# SDRAM_DDR3_4x16.net
KiCad netlist of a schematic drawn in Altium Designer
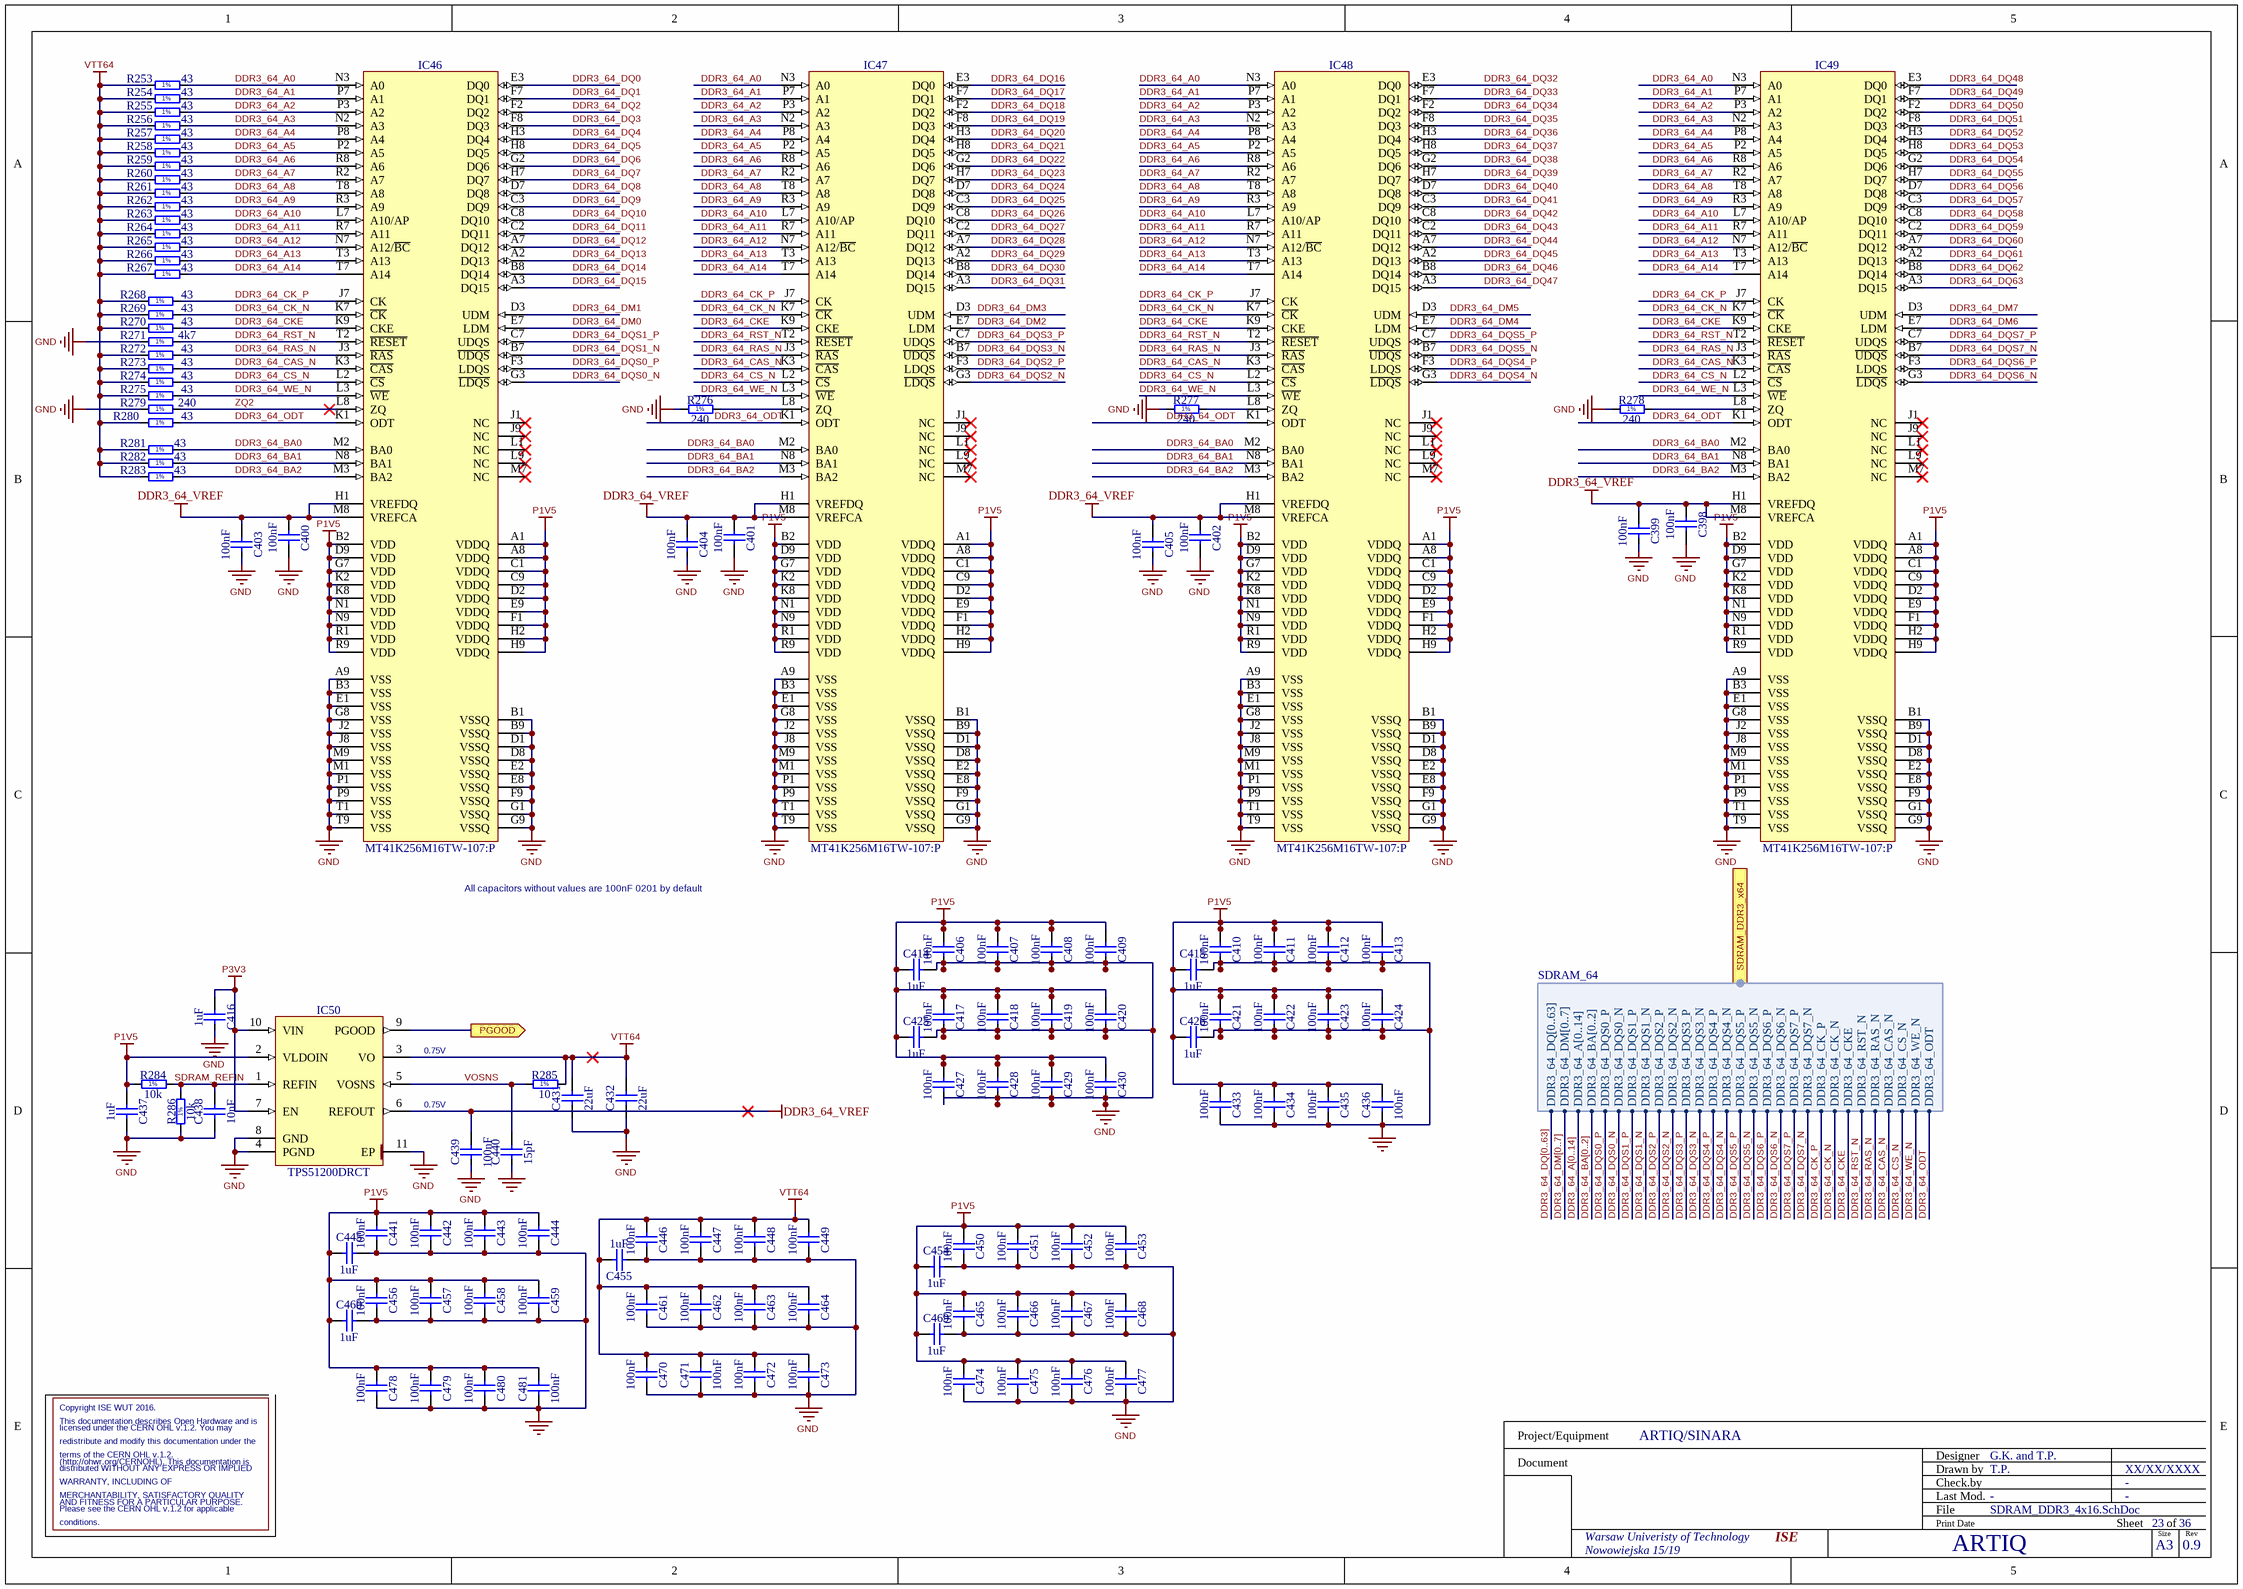
[diagram p0: SDRAM_DDR3_4x16.SchDoc]

(export (version "E")
  (design (tool "Eeschema 10.0.6"))
  (components
    (comp (ref "C398")
      (value "100nF")
      (footprint "CAPC0603X33N")
      (description "Non-polarised capacitor")
      (fields
        (field (name "MANUFACTURER PART NUMBER") "CC0201_100NF_6.3V_10%_X5R")
        (field (name "MANUFACTURER") "GENERIC")
        (field (name "AUTHOR") "CERN DEM JLC")
      )
      (libsource (lib "Capacitors") (part "Capacitor - non polarized"))
    )
    (comp (ref "C399")
      (value "100nF")
      (footprint "CAPC0603X33N")
      (description "Non-polarised capacitor")
      (fields
        (field (name "MANUFACTURER PART NUMBER") "CC0201_100NF_6.3V_10%_X5R")
        (field (name "MANUFACTURER") "GENERIC")
        (field (name "AUTHOR") "CERN DEM JLC")
      )
      (libsource (lib "Capacitors") (part "Capacitor - non polarized"))
    )
    (comp (ref "C400")
      (value "100nF")
      (footprint "CAPC0603X33N")
      (description "Non-polarised capacitor")
      (fields
        (field (name "MANUFACTURER PART NUMBER") "CC0201_100NF_6.3V_10%_X5R")
        (field (name "MANUFACTURER") "GENERIC")
        (field (name "AUTHOR") "CERN DEM JLC")
      )
      (libsource (lib "Capacitors") (part "Capacitor - non polarized"))
    )
    (comp (ref "C401")
      (value "100nF")
      (footprint "CAPC0603X33N")
      (description "Non-polarised capacitor")
      (fields
        (field (name "MANUFACTURER PART NUMBER") "CC0201_100NF_6.3V_10%_X5R")
        (field (name "MANUFACTURER") "GENERIC")
        (field (name "AUTHOR") "CERN DEM JLC")
      )
      (libsource (lib "Capacitors") (part "Capacitor - non polarized"))
    )
    (comp (ref "C402")
      (value "100nF")
      (footprint "CAPC0603X33N")
      (description "Non-polarised capacitor")
      (fields
        (field (name "MANUFACTURER PART NUMBER") "CC0201_100NF_6.3V_10%_X5R")
        (field (name "MANUFACTURER") "GENERIC")
        (field (name "AUTHOR") "CERN DEM JLC")
      )
      (libsource (lib "Capacitors") (part "Capacitor - non polarized"))
    )
    (comp (ref "C403")
      (value "100nF")
      (footprint "CAPC0603X33N")
      (description "Non-polarised capacitor")
      (fields
        (field (name "MANUFACTURER PART NUMBER") "CC0201_100NF_6.3V_10%_X5R")
        (field (name "MANUFACTURER") "GENERIC")
        (field (name "AUTHOR") "CERN DEM JLC")
      )
      (libsource (lib "Capacitors") (part "Capacitor - non polarized"))
    )
    (comp (ref "C404")
      (value "100nF")
      (footprint "CAPC0603X33N")
      (description "Non-polarised capacitor")
      (fields
        (field (name "MANUFACTURER PART NUMBER") "CC0201_100NF_6.3V_10%_X5R")
        (field (name "MANUFACTURER") "GENERIC")
        (field (name "AUTHOR") "CERN DEM JLC")
      )
      (libsource (lib "Capacitors") (part "Capacitor - non polarized"))
    )
    (comp (ref "C405")
      (value "100nF")
      (footprint "CAPC0603X33N")
      (description "Non-polarised capacitor")
      (fields
        (field (name "MANUFACTURER PART NUMBER") "CC0201_100NF_6.3V_10%_X5R")
        (field (name "MANUFACTURER") "GENERIC")
        (field (name "AUTHOR") "CERN DEM JLC")
      )
      (libsource (lib "Capacitors") (part "Capacitor - non polarized"))
    )
    (comp (ref "C406")
      (value "100nF")
      (footprint "CAPC0603X33N")
      (description "Non-polarised capacitor")
      (fields
        (field (name "MANUFACTURER PART NUMBER") "CC0201_100NF_6.3V_10%_X5R")
        (field (name "MANUFACTURER") "GENERIC")
        (field (name "AUTHOR") "CERN DEM JLC")
      )
      (libsource (lib "Capacitors") (part "Capacitor - non polarized"))
    )
    (comp (ref "C407")
      (value "100nF")
      (footprint "CAPC0603X33N")
      (description "Non-polarised capacitor")
      (fields
        (field (name "MANUFACTURER PART NUMBER") "CC0201_100NF_6.3V_10%_X5R")
        (field (name "MANUFACTURER") "GENERIC")
        (field (name "AUTHOR") "CERN DEM JLC")
      )
      (libsource (lib "Capacitors") (part "Capacitor - non polarized"))
    )
    (comp (ref "C408")
      (value "100nF")
      (footprint "CAPC0603X33N")
      (description "Non-polarised capacitor")
      (fields
        (field (name "MANUFACTURER PART NUMBER") "CC0201_100NF_6.3V_10%_X5R")
        (field (name "MANUFACTURER") "GENERIC")
        (field (name "AUTHOR") "CERN DEM JLC")
      )
      (libsource (lib "Capacitors") (part "Capacitor - non polarized"))
    )
    (comp (ref "C409")
      (value "100nF")
      (footprint "CAPC0603X33N")
      (description "Non-polarised capacitor")
      (fields
        (field (name "MANUFACTURER PART NUMBER") "CC0201_100NF_6.3V_10%_X5R")
        (field (name "MANUFACTURER") "GENERIC")
        (field (name "AUTHOR") "CERN DEM JLC")
      )
      (libsource (lib "Capacitors") (part "Capacitor - non polarized"))
    )
    (comp (ref "C410")
      (value "100nF")
      (footprint "CAPC0603X33N")
      (description "Non-polarised capacitor")
      (fields
        (field (name "MANUFACTURER PART NUMBER") "CC0201_100NF_6.3V_10%_X5R")
        (field (name "MANUFACTURER") "GENERIC")
        (field (name "AUTHOR") "CERN DEM JLC")
      )
      (libsource (lib "Capacitors") (part "Capacitor - non polarized"))
    )
    (comp (ref "C411")
      (value "100nF")
      (footprint "CAPC0603X33N")
      (description "Non-polarised capacitor")
      (fields
        (field (name "MANUFACTURER PART NUMBER") "CC0201_100NF_6.3V_10%_X5R")
        (field (name "MANUFACTURER") "GENERIC")
        (field (name "AUTHOR") "CERN DEM JLC")
      )
      (libsource (lib "Capacitors") (part "Capacitor - non polarized"))
    )
    (comp (ref "C412")
      (value "100nF")
      (footprint "CAPC0603X33N")
      (description "Non-polarised capacitor")
      (fields
        (field (name "MANUFACTURER PART NUMBER") "CC0201_100NF_6.3V_10%_X5R")
        (field (name "MANUFACTURER") "GENERIC")
        (field (name "AUTHOR") "CERN DEM JLC")
      )
      (libsource (lib "Capacitors") (part "Capacitor - non polarized"))
    )
    (comp (ref "C413")
      (value "100nF")
      (footprint "CAPC0603X33N")
      (description "Non-polarised capacitor")
      (fields
        (field (name "MANUFACTURER PART NUMBER") "CC0201_100NF_6.3V_10%_X5R")
        (field (name "MANUFACTURER") "GENERIC")
        (field (name "AUTHOR") "CERN DEM JLC")
      )
      (libsource (lib "Capacitors") (part "Capacitor - non polarized"))
    )
    (comp (ref "C414")
      (value "1uF")
      (footprint "CAPC1005X55N")
      (description "Non-polarised capacitor")
      (fields
        (field (name "MANUFACTURER PART NUMBER") "CC0402_1UF_16V_10%_X5R")
        (field (name "MANUFACTURER") "GENERIC")
        (field (name "AUTHOR") "CERN DEM JLC")
      )
      (libsource (lib "Capacitors") (part "Capacitor - non polarized"))
    )
    (comp (ref "C415")
      (value "1uF")
      (footprint "CAPC1005X55N")
      (description "Non-polarised capacitor")
      (fields
        (field (name "MANUFACTURER PART NUMBER") "CC0402_1UF_16V_10%_X5R")
        (field (name "MANUFACTURER") "GENERIC")
        (field (name "AUTHOR") "CERN DEM JLC")
      )
      (libsource (lib "Capacitors") (part "Capacitor - non polarized"))
    )
    (comp (ref "C416")
      (value "1uF")
      (footprint "CAPC1005X55N")
      (description "Non-polarised capacitor")
      (fields
        (field (name "MANUFACTURER PART NUMBER") "CC0402_1UF_16V_10%_X5R")
        (field (name "MANUFACTURER") "GENERIC")
        (field (name "AUTHOR") "CERN DEM JLC")
      )
      (libsource (lib "Capacitors") (part "Capacitor - non polarized"))
    )
    (comp (ref "C417")
      (value "100nF")
      (footprint "CAPC0603X33N")
      (description "Non-polarised capacitor")
      (fields
        (field (name "MANUFACTURER PART NUMBER") "CC0201_100NF_6.3V_10%_X5R")
        (field (name "MANUFACTURER") "GENERIC")
        (field (name "AUTHOR") "CERN DEM JLC")
      )
      (libsource (lib "Capacitors") (part "Capacitor - non polarized"))
    )
    (comp (ref "C418")
      (value "100nF")
      (footprint "CAPC0603X33N")
      (description "Non-polarised capacitor")
      (fields
        (field (name "MANUFACTURER PART NUMBER") "CC0201_100NF_6.3V_10%_X5R")
        (field (name "MANUFACTURER") "GENERIC")
        (field (name "AUTHOR") "CERN DEM JLC")
      )
      (libsource (lib "Capacitors") (part "Capacitor - non polarized"))
    )
    (comp (ref "C419")
      (value "100nF")
      (footprint "CAPC0603X33N")
      (description "Non-polarised capacitor")
      (fields
        (field (name "MANUFACTURER PART NUMBER") "CC0201_100NF_6.3V_10%_X5R")
        (field (name "MANUFACTURER") "GENERIC")
        (field (name "AUTHOR") "CERN DEM JLC")
      )
      (libsource (lib "Capacitors") (part "Capacitor - non polarized"))
    )
    (comp (ref "C420")
      (value "100nF")
      (footprint "CAPC0603X33N")
      (description "Non-polarised capacitor")
      (fields
        (field (name "MANUFACTURER PART NUMBER") "CC0201_100NF_6.3V_10%_X5R")
        (field (name "MANUFACTURER") "GENERIC")
        (field (name "AUTHOR") "CERN DEM JLC")
      )
      (libsource (lib "Capacitors") (part "Capacitor - non polarized"))
    )
    (comp (ref "C421")
      (value "100nF")
      (footprint "CAPC0603X33N")
      (description "Non-polarised capacitor")
      (fields
        (field (name "MANUFACTURER PART NUMBER") "CC0201_100NF_6.3V_10%_X5R")
        (field (name "MANUFACTURER") "GENERIC")
        (field (name "AUTHOR") "CERN DEM JLC")
      )
      (libsource (lib "Capacitors") (part "Capacitor - non polarized"))
    )
    (comp (ref "C422")
      (value "100nF")
      (footprint "CAPC0603X33N")
      (description "Non-polarised capacitor")
      (fields
        (field (name "MANUFACTURER PART NUMBER") "CC0201_100NF_6.3V_10%_X5R")
        (field (name "MANUFACTURER") "GENERIC")
        (field (name "AUTHOR") "CERN DEM JLC")
      )
      (libsource (lib "Capacitors") (part "Capacitor - non polarized"))
    )
    (comp (ref "C423")
      (value "100nF")
      (footprint "CAPC0603X33N")
      (description "Non-polarised capacitor")
      (fields
        (field (name "MANUFACTURER PART NUMBER") "CC0201_100NF_6.3V_10%_X5R")
        (field (name "MANUFACTURER") "GENERIC")
        (field (name "AUTHOR") "CERN DEM JLC")
      )
      (libsource (lib "Capacitors") (part "Capacitor - non polarized"))
    )
    (comp (ref "C424")
      (value "100nF")
      (footprint "CAPC0603X33N")
      (description "Non-polarised capacitor")
      (fields
        (field (name "MANUFACTURER PART NUMBER") "CC0201_100NF_6.3V_10%_X5R")
        (field (name "MANUFACTURER") "GENERIC")
        (field (name "AUTHOR") "CERN DEM JLC")
      )
      (libsource (lib "Capacitors") (part "Capacitor - non polarized"))
    )
    (comp (ref "C425")
      (value "1uF")
      (footprint "CAPC1005X55N")
      (description "Non-polarised capacitor")
      (fields
        (field (name "MANUFACTURER PART NUMBER") "CC0402_1UF_16V_10%_X5R")
        (field (name "MANUFACTURER") "GENERIC")
        (field (name "AUTHOR") "CERN DEM JLC")
      )
      (libsource (lib "Capacitors") (part "Capacitor - non polarized"))
    )
    (comp (ref "C426")
      (value "1uF")
      (footprint "CAPC1005X55N")
      (description "Non-polarised capacitor")
      (fields
        (field (name "MANUFACTURER PART NUMBER") "CC0402_1UF_16V_10%_X5R")
        (field (name "MANUFACTURER") "GENERIC")
        (field (name "AUTHOR") "CERN DEM JLC")
      )
      (libsource (lib "Capacitors") (part "Capacitor - non polarized"))
    )
    (comp (ref "C427")
      (value "100nF")
      (footprint "CAPC0603X33N")
      (description "Non-polarised capacitor")
      (fields
        (field (name "MANUFACTURER PART NUMBER") "CC0201_100NF_6.3V_10%_X5R")
        (field (name "MANUFACTURER") "GENERIC")
        (field (name "AUTHOR") "CERN DEM JLC")
      )
      (libsource (lib "Capacitors") (part "Capacitor - non polarized"))
    )
    (comp (ref "C428")
      (value "100nF")
      (footprint "CAPC0603X33N")
      (description "Non-polarised capacitor")
      (fields
        (field (name "MANUFACTURER PART NUMBER") "CC0201_100NF_6.3V_10%_X5R")
        (field (name "MANUFACTURER") "GENERIC")
        (field (name "AUTHOR") "CERN DEM JLC")
      )
      (libsource (lib "Capacitors") (part "Capacitor - non polarized"))
    )
    (comp (ref "C429")
      (value "100nF")
      (footprint "CAPC0603X33N")
      (description "Non-polarised capacitor")
      (fields
        (field (name "MANUFACTURER PART NUMBER") "CC0201_100NF_6.3V_10%_X5R")
        (field (name "MANUFACTURER") "GENERIC")
        (field (name "AUTHOR") "CERN DEM JLC")
      )
      (libsource (lib "Capacitors") (part "Capacitor - non polarized"))
    )
    (comp (ref "C430")
      (value "100nF")
      (footprint "CAPC0603X33N")
      (description "Non-polarised capacitor")
      (fields
        (field (name "MANUFACTURER PART NUMBER") "CC0201_100NF_6.3V_10%_X5R")
        (field (name "MANUFACTURER") "GENERIC")
        (field (name "AUTHOR") "CERN DEM JLC")
      )
      (libsource (lib "Capacitors") (part "Capacitor - non polarized"))
    )
    (comp (ref "C431")
      (value "22uF")
      (footprint "CAPC2012X135N")
      (description "Non-polarised capacitor")
      (fields
        (field (name "MANUFACTURER PART NUMBER") "CC0805_22UF_10V_+80%-20%_Y5V")
        (field (name "MANUFACTURER") "GENERIC")
        (field (name "AUTHOR") "CERN DEM JLC")
      )
      (libsource (lib "Capacitors") (part "Capacitor - non polarized"))
    )
    (comp (ref "C432")
      (value "22uF")
      (footprint "CAPC2012X135N")
      (description "Non-polarised capacitor")
      (fields
        (field (name "MANUFACTURER PART NUMBER") "CC0805_22UF_10V_+80%-20%_Y5V")
        (field (name "MANUFACTURER") "GENERIC")
        (field (name "AUTHOR") "CERN DEM JLC")
      )
      (libsource (lib "Capacitors") (part "Capacitor - non polarized"))
    )
    (comp (ref "C433")
      (value "100nF")
      (footprint "CAPC0603X33N")
      (description "Non-polarised capacitor")
      (fields
        (field (name "MANUFACTURER PART NUMBER") "CC0201_100NF_6.3V_10%_X5R")
        (field (name "MANUFACTURER") "GENERIC")
        (field (name "AUTHOR") "CERN DEM JLC")
      )
      (libsource (lib "Capacitors") (part "Capacitor - non polarized"))
    )
    (comp (ref "C434")
      (value "100nF")
      (footprint "CAPC0603X33N")
      (description "Non-polarised capacitor")
      (fields
        (field (name "MANUFACTURER PART NUMBER") "CC0201_100NF_6.3V_10%_X5R")
        (field (name "MANUFACTURER") "GENERIC")
        (field (name "AUTHOR") "CERN DEM JLC")
      )
      (libsource (lib "Capacitors") (part "Capacitor - non polarized"))
    )
    (comp (ref "C435")
      (value "100nF")
      (footprint "CAPC0603X33N")
      (description "Non-polarised capacitor")
      (fields
        (field (name "MANUFACTURER PART NUMBER") "CC0201_100NF_6.3V_10%_X5R")
        (field (name "MANUFACTURER") "GENERIC")
        (field (name "AUTHOR") "CERN DEM JLC")
      )
      (libsource (lib "Capacitors") (part "Capacitor - non polarized"))
    )
    (comp (ref "C436")
      (value "100nF")
      (footprint "CAPC0603X33N")
      (description "Non-polarised capacitor")
      (fields
        (field (name "MANUFACTURER PART NUMBER") "CC0201_100NF_6.3V_10%_X5R")
        (field (name "MANUFACTURER") "GENERIC")
        (field (name "AUTHOR") "CERN DEM JLC")
      )
      (libsource (lib "Capacitors") (part "Capacitor - non polarized"))
    )
    (comp (ref "C437")
      (value "1uF")
      (footprint "CAPC1005X55N")
      (description "Non-polarised capacitor")
      (fields
        (field (name "MANUFACTURER PART NUMBER") "CC0402_1UF_16V_10%_X5R")
        (field (name "MANUFACTURER") "GENERIC")
        (field (name "AUTHOR") "CERN DEM JLC")
      )
      (libsource (lib "Capacitors") (part "Capacitor - non polarized"))
    )
    (comp (ref "C438")
      (value "10nF")
      (footprint "CAPC1005X55N")
      (description "Non-polarised capacitor")
      (fields
        (field (name "MANUFACTURER PART NUMBER") "CC0402_10NF_25V_10%_X7R")
        (field (name "MANUFACTURER") "GENERIC")
        (field (name "AUTHOR") "CERN DEM JLC")
      )
      (libsource (lib "Capacitors") (part "Capacitor - non polarized"))
    )
    (comp (ref "C439")
      (value "100nF")
      (footprint "CAPC0603X33N")
      (description "Non-polarised capacitor")
      (fields
        (field (name "MANUFACTURER PART NUMBER") "CC0201_100NF_6.3V_10%_X5R")
        (field (name "MANUFACTURER") "GENERIC")
        (field (name "AUTHOR") "CERN DEM JLC")
      )
      (libsource (lib "Capacitors") (part "Capacitor - non polarized"))
    )
    (comp (ref "C440")
      (value "15pF")
      (footprint "CAPC1005X55N")
      (description "Non-polarised capacitor")
      (fields
        (field (name "MANUFACTURER PART NUMBER") "CC0402_15PF_50V_5%_C0G")
        (field (name "MANUFACTURER") "GENERIC")
        (field (name "AUTHOR") "CERN DEM JLC")
      )
      (libsource (lib "Capacitors") (part "Capacitor - non polarized"))
    )
    (comp (ref "C441")
      (value "100nF")
      (footprint "CAPC0603X33N")
      (description "Non-polarised capacitor")
      (fields
        (field (name "MANUFACTURER PART NUMBER") "CC0201_100NF_6.3V_10%_X5R")
        (field (name "MANUFACTURER") "GENERIC")
        (field (name "AUTHOR") "CERN DEM JLC")
      )
      (libsource (lib "Capacitors") (part "Capacitor - non polarized"))
    )
    (comp (ref "C442")
      (value "100nF")
      (footprint "CAPC0603X33N")
      (description "Non-polarised capacitor")
      (fields
        (field (name "MANUFACTURER PART NUMBER") "CC0201_100NF_6.3V_10%_X5R")
        (field (name "MANUFACTURER") "GENERIC")
        (field (name "AUTHOR") "CERN DEM JLC")
      )
      (libsource (lib "Capacitors") (part "Capacitor - non polarized"))
    )
    (comp (ref "C443")
      (value "100nF")
      (footprint "CAPC0603X33N")
      (description "Non-polarised capacitor")
      (fields
        (field (name "MANUFACTURER PART NUMBER") "CC0201_100NF_6.3V_10%_X5R")
        (field (name "MANUFACTURER") "GENERIC")
        (field (name "AUTHOR") "CERN DEM JLC")
      )
      (libsource (lib "Capacitors") (part "Capacitor - non polarized"))
    )
    (comp (ref "C444")
      (value "100nF")
      (footprint "CAPC0603X33N")
      (description "Non-polarised capacitor")
      (fields
        (field (name "MANUFACTURER PART NUMBER") "CC0201_100NF_6.3V_10%_X5R")
        (field (name "MANUFACTURER") "GENERIC")
        (field (name "AUTHOR") "CERN DEM JLC")
      )
      (libsource (lib "Capacitors") (part "Capacitor - non polarized"))
    )
    (comp (ref "C445")
      (value "1uF")
      (footprint "CAPC1005X55N")
      (description "Non-polarised capacitor")
      (fields
        (field (name "MANUFACTURER PART NUMBER") "CC0402_1UF_16V_10%_X5R")
        (field (name "MANUFACTURER") "GENERIC")
        (field (name "AUTHOR") "CERN DEM JLC")
      )
      (libsource (lib "Capacitors") (part "Capacitor - non polarized"))
    )
    (comp (ref "C446")
      (value "100nF")
      (footprint "CAPC0603X33N")
      (description "Non-polarised capacitor")
      (fields
        (field (name "MANUFACTURER PART NUMBER") "CC0201_100NF_6.3V_10%_X5R")
        (field (name "MANUFACTURER") "GENERIC")
        (field (name "AUTHOR") "CERN DEM JLC")
      )
      (libsource (lib "Capacitors") (part "Capacitor - non polarized"))
    )
    (comp (ref "C447")
      (value "100nF")
      (footprint "CAPC0603X33N")
      (description "Non-polarised capacitor")
      (fields
        (field (name "MANUFACTURER PART NUMBER") "CC0201_100NF_6.3V_10%_X5R")
        (field (name "MANUFACTURER") "GENERIC")
        (field (name "AUTHOR") "CERN DEM JLC")
      )
      (libsource (lib "Capacitors") (part "Capacitor - non polarized"))
    )
    (comp (ref "C448")
      (value "100nF")
      (footprint "CAPC0603X33N")
      (description "Non-polarised capacitor")
      (fields
        (field (name "MANUFACTURER PART NUMBER") "CC0201_100NF_6.3V_10%_X5R")
        (field (name "MANUFACTURER") "GENERIC")
        (field (name "AUTHOR") "CERN DEM JLC")
      )
      (libsource (lib "Capacitors") (part "Capacitor - non polarized"))
    )
    (comp (ref "C449")
      (value "100nF")
      (footprint "CAPC0603X33N")
      (description "Non-polarised capacitor")
      (fields
        (field (name "MANUFACTURER PART NUMBER") "CC0201_100NF_6.3V_10%_X5R")
        (field (name "MANUFACTURER") "GENERIC")
        (field (name "AUTHOR") "CERN DEM JLC")
      )
      (libsource (lib "Capacitors") (part "Capacitor - non polarized"))
    )
    (comp (ref "C450")
      (value "100nF")
      (footprint "CAPC0603X33N")
      (description "Non-polarised capacitor")
      (fields
        (field (name "MANUFACTURER PART NUMBER") "CC0201_100NF_6.3V_10%_X5R")
        (field (name "MANUFACTURER") "GENERIC")
        (field (name "AUTHOR") "CERN DEM JLC")
      )
      (libsource (lib "Capacitors") (part "Capacitor - non polarized"))
    )
    (comp (ref "C451")
      (value "100nF")
      (footprint "CAPC0603X33N")
      (description "Non-polarised capacitor")
      (fields
        (field (name "MANUFACTURER PART NUMBER") "CC0201_100NF_6.3V_10%_X5R")
        (field (name "MANUFACTURER") "GENERIC")
        (field (name "AUTHOR") "CERN DEM JLC")
      )
      (libsource (lib "Capacitors") (part "Capacitor - non polarized"))
    )
    (comp (ref "C452")
      (value "100nF")
      (footprint "CAPC0603X33N")
      (description "Non-polarised capacitor")
      (fields
        (field (name "MANUFACTURER PART NUMBER") "CC0201_100NF_6.3V_10%_X5R")
        (field (name "MANUFACTURER") "GENERIC")
        (field (name "AUTHOR") "CERN DEM JLC")
      )
      (libsource (lib "Capacitors") (part "Capacitor - non polarized"))
    )
    (comp (ref "C453")
      (value "100nF")
      (footprint "CAPC0603X33N")
      (description "Non-polarised capacitor")
      (fields
        (field (name "MANUFACTURER PART NUMBER") "CC0201_100NF_6.3V_10%_X5R")
        (field (name "MANUFACTURER") "GENERIC")
        (field (name "AUTHOR") "CERN DEM JLC")
      )
      (libsource (lib "Capacitors") (part "Capacitor - non polarized"))
    )
    (comp (ref "C454")
      (value "1uF")
      (footprint "CAPC1005X55N")
      (description "Non-polarised capacitor")
      (fields
        (field (name "MANUFACTURER PART NUMBER") "CC0402_1UF_16V_10%_X5R")
        (field (name "MANUFACTURER") "GENERIC")
        (field (name "AUTHOR") "CERN DEM JLC")
      )
      (libsource (lib "Capacitors") (part "Capacitor - non polarized"))
    )
    (comp (ref "C455")
      (value "1uF")
      (footprint "CAPC1005X55N")
      (description "Non-polarised capacitor")
      (fields
        (field (name "MANUFACTURER PART NUMBER") "CC0402_1UF_16V_10%_X5R")
        (field (name "MANUFACTURER") "GENERIC")
        (field (name "AUTHOR") "CERN DEM JLC")
      )
      (libsource (lib "Capacitors") (part "Capacitor - non polarized"))
    )
    (comp (ref "C456")
      (value "100nF")
      (footprint "CAPC0603X33N")
      (description "Non-polarised capacitor")
      (fields
        (field (name "MANUFACTURER PART NUMBER") "CC0201_100NF_6.3V_10%_X5R")
        (field (name "MANUFACTURER") "GENERIC")
        (field (name "AUTHOR") "CERN DEM JLC")
      )
      (libsource (lib "Capacitors") (part "Capacitor - non polarized"))
    )
    (comp (ref "C457")
      (value "100nF")
      (footprint "CAPC0603X33N")
      (description "Non-polarised capacitor")
      (fields
        (field (name "MANUFACTURER PART NUMBER") "CC0201_100NF_6.3V_10%_X5R")
        (field (name "MANUFACTURER") "GENERIC")
        (field (name "AUTHOR") "CERN DEM JLC")
      )
      (libsource (lib "Capacitors") (part "Capacitor - non polarized"))
    )
    (comp (ref "C458")
      (value "100nF")
      (footprint "CAPC0603X33N")
      (description "Non-polarised capacitor")
      (fields
        (field (name "MANUFACTURER PART NUMBER") "CC0201_100NF_6.3V_10%_X5R")
        (field (name "MANUFACTURER") "GENERIC")
        (field (name "AUTHOR") "CERN DEM JLC")
      )
      (libsource (lib "Capacitors") (part "Capacitor - non polarized"))
    )
    (comp (ref "C459")
      (value "100nF")
      (footprint "CAPC0603X33N")
      (description "Non-polarised capacitor")
      (fields
        (field (name "MANUFACTURER PART NUMBER") "CC0201_100NF_6.3V_10%_X5R")
        (field (name "MANUFACTURER") "GENERIC")
        (field (name "AUTHOR") "CERN DEM JLC")
      )
      (libsource (lib "Capacitors") (part "Capacitor - non polarized"))
    )
    (comp (ref "C460")
      (value "1uF")
      (footprint "CAPC1005X55N")
      (description "Non-polarised capacitor")
      (fields
        (field (name "MANUFACTURER PART NUMBER") "CC0402_1UF_16V_10%_X5R")
        (field (name "MANUFACTURER") "GENERIC")
        (field (name "AUTHOR") "CERN DEM JLC")
      )
      (libsource (lib "Capacitors") (part "Capacitor - non polarized"))
    )
    (comp (ref "C461")
      (value "100nF")
      (footprint "CAPC0603X33N")
      (description "Non-polarised capacitor")
      (fields
        (field (name "MANUFACTURER PART NUMBER") "CC0201_100NF_6.3V_10%_X5R")
        (field (name "MANUFACTURER") "GENERIC")
        (field (name "AUTHOR") "CERN DEM JLC")
      )
      (libsource (lib "Capacitors") (part "Capacitor - non polarized"))
    )
    (comp (ref "C462")
      (value "100nF")
      (footprint "CAPC0603X33N")
      (description "Non-polarised capacitor")
      (fields
        (field (name "MANUFACTURER PART NUMBER") "CC0201_100NF_6.3V_10%_X5R")
        (field (name "MANUFACTURER") "GENERIC")
        (field (name "AUTHOR") "CERN DEM JLC")
      )
      (libsource (lib "Capacitors") (part "Capacitor - non polarized"))
    )
    (comp (ref "C463")
      (value "100nF")
      (footprint "CAPC0603X33N")
      (description "Non-polarised capacitor")
      (fields
        (field (name "MANUFACTURER PART NUMBER") "CC0201_100NF_6.3V_10%_X5R")
        (field (name "MANUFACTURER") "GENERIC")
        (field (name "AUTHOR") "CERN DEM JLC")
      )
      (libsource (lib "Capacitors") (part "Capacitor - non polarized"))
    )
    (comp (ref "C464")
      (value "100nF")
      (footprint "CAPC0603X33N")
      (description "Non-polarised capacitor")
      (fields
        (field (name "MANUFACTURER PART NUMBER") "CC0201_100NF_6.3V_10%_X5R")
        (field (name "MANUFACTURER") "GENERIC")
        (field (name "AUTHOR") "CERN DEM JLC")
      )
      (libsource (lib "Capacitors") (part "Capacitor - non polarized"))
    )
    (comp (ref "C465")
      (value "100nF")
      (footprint "CAPC0603X33N")
      (description "Non-polarised capacitor")
      (fields
        (field (name "MANUFACTURER PART NUMBER") "CC0201_100NF_6.3V_10%_X5R")
        (field (name "MANUFACTURER") "GENERIC")
        (field (name "AUTHOR") "CERN DEM JLC")
      )
      (libsource (lib "Capacitors") (part "Capacitor - non polarized"))
    )
    (comp (ref "C466")
      (value "100nF")
      (footprint "CAPC0603X33N")
      (description "Non-polarised capacitor")
      (fields
        (field (name "MANUFACTURER PART NUMBER") "CC0201_100NF_6.3V_10%_X5R")
        (field (name "MANUFACTURER") "GENERIC")
        (field (name "AUTHOR") "CERN DEM JLC")
      )
      (libsource (lib "Capacitors") (part "Capacitor - non polarized"))
    )
    (comp (ref "C467")
      (value "100nF")
      (footprint "CAPC0603X33N")
      (description "Non-polarised capacitor")
      (fields
        (field (name "MANUFACTURER PART NUMBER") "CC0201_100NF_6.3V_10%_X5R")
        (field (name "MANUFACTURER") "GENERIC")
        (field (name "AUTHOR") "CERN DEM JLC")
      )
      (libsource (lib "Capacitors") (part "Capacitor - non polarized"))
    )
    (comp (ref "C468")
      (value "100nF")
      (footprint "CAPC0603X33N")
      (description "Non-polarised capacitor")
      (fields
        (field (name "MANUFACTURER PART NUMBER") "CC0201_100NF_6.3V_10%_X5R")
        (field (name "MANUFACTURER") "GENERIC")
        (field (name "AUTHOR") "CERN DEM JLC")
      )
      (libsource (lib "Capacitors") (part "Capacitor - non polarized"))
    )
    (comp (ref "C469")
      (value "1uF")
      (footprint "CAPC1005X55N")
      (description "Non-polarised capacitor")
      (fields
        (field (name "MANUFACTURER PART NUMBER") "CC0402_1UF_16V_10%_X5R")
        (field (name "MANUFACTURER") "GENERIC")
        (field (name "AUTHOR") "CERN DEM JLC")
      )
      (libsource (lib "Capacitors") (part "Capacitor - non polarized"))
    )
    (comp (ref "C470")
      (value "100nF")
      (footprint "CAPC0603X33N")
      (description "Non-polarised capacitor")
      (fields
        (field (name "MANUFACTURER PART NUMBER") "CC0201_100NF_6.3V_10%_X5R")
        (field (name "MANUFACTURER") "GENERIC")
        (field (name "AUTHOR") "CERN DEM JLC")
      )
      (libsource (lib "Capacitors") (part "Capacitor - non polarized"))
    )
    (comp (ref "C471")
      (value "100nF")
      (footprint "CAPC0603X33N")
      (description "Non-polarised capacitor")
      (fields
        (field (name "MANUFACTURER PART NUMBER") "CC0201_100NF_6.3V_10%_X5R")
        (field (name "MANUFACTURER") "GENERIC")
        (field (name "AUTHOR") "CERN DEM JLC")
      )
      (libsource (lib "Capacitors") (part "Capacitor - non polarized"))
    )
    (comp (ref "C472")
      (value "100nF")
      (footprint "CAPC0603X33N")
      (description "Non-polarised capacitor")
      (fields
        (field (name "MANUFACTURER PART NUMBER") "CC0201_100NF_6.3V_10%_X5R")
        (field (name "MANUFACTURER") "GENERIC")
        (field (name "AUTHOR") "CERN DEM JLC")
      )
      (libsource (lib "Capacitors") (part "Capacitor - non polarized"))
    )
    (comp (ref "C473")
      (value "100nF")
      (footprint "CAPC0603X33N")
      (description "Non-polarised capacitor")
      (fields
        (field (name "MANUFACTURER PART NUMBER") "CC0201_100NF_6.3V_10%_X5R")
        (field (name "MANUFACTURER") "GENERIC")
        (field (name "AUTHOR") "CERN DEM JLC")
      )
      (libsource (lib "Capacitors") (part "Capacitor - non polarized"))
    )
    (comp (ref "C474")
      (value "100nF")
      (footprint "CAPC0603X33N")
      (description "Non-polarised capacitor")
      (fields
        (field (name "MANUFACTURER PART NUMBER") "CC0201_100NF_6.3V_10%_X5R")
        (field (name "MANUFACTURER") "GENERIC")
        (field (name "AUTHOR") "CERN DEM JLC")
      )
      (libsource (lib "Capacitors") (part "Capacitor - non polarized"))
    )
    (comp (ref "C475")
      (value "100nF")
      (footprint "CAPC0603X33N")
      (description "Non-polarised capacitor")
      (fields
        (field (name "MANUFACTURER PART NUMBER") "CC0201_100NF_6.3V_10%_X5R")
        (field (name "MANUFACTURER") "GENERIC")
        (field (name "AUTHOR") "CERN DEM JLC")
      )
      (libsource (lib "Capacitors") (part "Capacitor - non polarized"))
    )
    (comp (ref "C476")
      (value "100nF")
      (footprint "CAPC0603X33N")
      (description "Non-polarised capacitor")
      (fields
        (field (name "MANUFACTURER PART NUMBER") "CC0201_100NF_6.3V_10%_X5R")
        (field (name "MANUFACTURER") "GENERIC")
        (field (name "AUTHOR") "CERN DEM JLC")
      )
      (libsource (lib "Capacitors") (part "Capacitor - non polarized"))
    )
    (comp (ref "C477")
      (value "100nF")
      (footprint "CAPC0603X33N")
      (description "Non-polarised capacitor")
      (fields
        (field (name "MANUFACTURER PART NUMBER") "CC0201_100NF_6.3V_10%_X5R")
        (field (name "MANUFACTURER") "GENERIC")
        (field (name "AUTHOR") "CERN DEM JLC")
      )
      (libsource (lib "Capacitors") (part "Capacitor - non polarized"))
    )
    (comp (ref "C478")
      (value "100nF")
      (footprint "CAPC0603X33N")
      (description "Non-polarised capacitor")
      (fields
        (field (name "MANUFACTURER PART NUMBER") "CC0201_100NF_6.3V_10%_X5R")
        (field (name "MANUFACTURER") "GENERIC")
        (field (name "AUTHOR") "CERN DEM JLC")
      )
      (libsource (lib "Capacitors") (part "Capacitor - non polarized"))
    )
    (comp (ref "C479")
      (value "100nF")
      (footprint "CAPC0603X33N")
      (description "Non-polarised capacitor")
      (fields
        (field (name "MANUFACTURER PART NUMBER") "CC0201_100NF_6.3V_10%_X5R")
        (field (name "MANUFACTURER") "GENERIC")
        (field (name "AUTHOR") "CERN DEM JLC")
      )
      (libsource (lib "Capacitors") (part "Capacitor - non polarized"))
    )
    (comp (ref "C480")
      (value "100nF")
      (footprint "CAPC0603X33N")
      (description "Non-polarised capacitor")
      (fields
        (field (name "MANUFACTURER PART NUMBER") "CC0201_100NF_6.3V_10%_X5R")
        (field (name "MANUFACTURER") "GENERIC")
        (field (name "AUTHOR") "CERN DEM JLC")
      )
      (libsource (lib "Capacitors") (part "Capacitor - non polarized"))
    )
    (comp (ref "C481")
      (value "100nF")
      (footprint "CAPC0603X33N")
      (description "Non-polarised capacitor")
      (fields
        (field (name "MANUFACTURER PART NUMBER") "CC0201_100NF_6.3V_10%_X5R")
        (field (name "MANUFACTURER") "GENERIC")
        (field (name "AUTHOR") "CERN DEM JLC")
      )
      (libsource (lib "Capacitors") (part "Capacitor - non polarized"))
    )
    (comp (ref "IC46")
      (value "MT41K256M16TW-107:P")
      (footprint "BGA96C80P9X16_800X1400X120")
      (description "32 Meg x 16 x 8 Banks DDR3L SDRAM")
      (fields (field (name "MANUFACTURER") "MICRON TECHNOLOGY") (field (name "AUTHOR") "CERN DEM MR"))
      (libsource (lib "ICs And Semiconductors") (part "MT41K256M16TW-107{colon}P"))
    )
    (comp (ref "IC47")
      (value "MT41K256M16TW-107:P")
      (footprint "BGA96C80P9X16_800X1400X120")
      (description "32 Meg x 16 x 8 Banks DDR3L SDRAM")
      (fields (field (name "MANUFACTURER") "MICRON TECHNOLOGY") (field (name "AUTHOR") "CERN DEM MR"))
      (libsource (lib "ICs And Semiconductors") (part "MT41K256M16TW-107{colon}P"))
    )
    (comp (ref "IC48")
      (value "MT41K256M16TW-107:P")
      (footprint "BGA96C80P9X16_800X1400X120")
      (description "32 Meg x 16 x 8 Banks DDR3L SDRAM")
      (fields (field (name "MANUFACTURER") "MICRON TECHNOLOGY") (field (name "AUTHOR") "CERN DEM MR"))
      (libsource (lib "ICs And Semiconductors") (part "MT41K256M16TW-107{colon}P"))
    )
    (comp (ref "IC49")
      (value "MT41K256M16TW-107:P")
      (footprint "BGA96C80P9X16_800X1400X120")
      (description "32 Meg x 16 x 8 Banks DDR3L SDRAM")
      (fields (field (name "MANUFACTURER") "MICRON TECHNOLOGY") (field (name "AUTHOR") "CERN DEM MR"))
      (libsource (lib "ICs And Semiconductors") (part "MT41K256M16TW-107{colon}P"))
    )
    (comp (ref "IC50")
      (value "TPS51200DRCT")
      (footprint "TEXAS_DRC (S-PVSON-N10)")
      (description "Sink/Source DDR Termination Regulator")
      (fields (field (name "MANUFACTURER") "TEXAS INSTRUMENTS") (field (name "AUTHOR") "CERN DEM JLC"))
      (libsource (lib "ICs And Semiconductors") (part "TPS51200DRC"))
    )
    (comp (ref "R253")
      (value "43")
      (footprint "RESC1005X40N")
      (description "Resistor - 1%")
      (fields
        (field (name "MANUFACTURER PART NUMBER") "R0402_43R_1%_0.0625W_100PPM")
        (field (name "MANUFACTURER") "GENERIC")
        (field (name "AUTHOR") "CERN DEM JLC")
      )
      (libsource (lib "Resistors") (part "Resistor - 1%"))
    )
    (comp (ref "R254")
      (value "43")
      (footprint "RESC1005X40N")
      (description "Resistor - 1%")
      (fields
        (field (name "MANUFACTURER PART NUMBER") "R0402_43R_1%_0.0625W_100PPM")
        (field (name "MANUFACTURER") "GENERIC")
        (field (name "AUTHOR") "CERN DEM JLC")
      )
      (libsource (lib "Resistors") (part "Resistor - 1%"))
    )
    (comp (ref "R255")
      (value "43")
      (footprint "RESC1005X40N")
      (description "Resistor - 1%")
      (fields
        (field (name "MANUFACTURER PART NUMBER") "R0402_43R_1%_0.0625W_100PPM")
        (field (name "MANUFACTURER") "GENERIC")
        (field (name "AUTHOR") "CERN DEM JLC")
      )
      (libsource (lib "Resistors") (part "Resistor - 1%"))
    )
    (comp (ref "R256")
      (value "43")
      (footprint "RESC1005X40N")
      (description "Resistor - 1%")
      (fields
        (field (name "MANUFACTURER PART NUMBER") "R0402_43R_1%_0.0625W_100PPM")
        (field (name "MANUFACTURER") "GENERIC")
        (field (name "AUTHOR") "CERN DEM JLC")
      )
      (libsource (lib "Resistors") (part "Resistor - 1%"))
    )
    (comp (ref "R257")
      (value "43")
      (footprint "RESC1005X40N")
      (description "Resistor - 1%")
      (fields
        (field (name "MANUFACTURER PART NUMBER") "R0402_43R_1%_0.0625W_100PPM")
        (field (name "MANUFACTURER") "GENERIC")
        (field (name "AUTHOR") "CERN DEM JLC")
      )
      (libsource (lib "Resistors") (part "Resistor - 1%"))
    )
    (comp (ref "R258")
      (value "43")
      (footprint "RESC1005X40N")
      (description "Resistor - 1%")
      (fields
        (field (name "MANUFACTURER PART NUMBER") "R0402_43R_1%_0.0625W_100PPM")
        (field (name "MANUFACTURER") "GENERIC")
        (field (name "AUTHOR") "CERN DEM JLC")
      )
      (libsource (lib "Resistors") (part "Resistor - 1%"))
    )
    (comp (ref "R259")
      (value "43")
      (footprint "RESC1005X40N")
      (description "Resistor - 1%")
      (fields
        (field (name "MANUFACTURER PART NUMBER") "R0402_43R_1%_0.0625W_100PPM")
        (field (name "MANUFACTURER") "GENERIC")
        (field (name "AUTHOR") "CERN DEM JLC")
      )
      (libsource (lib "Resistors") (part "Resistor - 1%"))
    )
    (comp (ref "R260")
      (value "43")
      (footprint "RESC1005X40N")
      (description "Resistor - 1%")
      (fields
        (field (name "MANUFACTURER PART NUMBER") "R0402_43R_1%_0.0625W_100PPM")
        (field (name "MANUFACTURER") "GENERIC")
        (field (name "AUTHOR") "CERN DEM JLC")
      )
      (libsource (lib "Resistors") (part "Resistor - 1%"))
    )
    (comp (ref "R261")
      (value "43")
      (footprint "RESC1005X40N")
      (description "Resistor - 1%")
      (fields
        (field (name "MANUFACTURER PART NUMBER") "R0402_43R_1%_0.0625W_100PPM")
        (field (name "MANUFACTURER") "GENERIC")
        (field (name "AUTHOR") "CERN DEM JLC")
      )
      (libsource (lib "Resistors") (part "Resistor - 1%"))
    )
    (comp (ref "R262")
      (value "43")
      (footprint "RESC1005X40N")
      (description "Resistor - 1%")
      (fields
        (field (name "MANUFACTURER PART NUMBER") "R0402_43R_1%_0.0625W_100PPM")
        (field (name "MANUFACTURER") "GENERIC")
        (field (name "AUTHOR") "CERN DEM JLC")
      )
      (libsource (lib "Resistors") (part "Resistor - 1%"))
    )
    (comp (ref "R263")
      (value "43")
      (footprint "RESC1005X40N")
      (description "Resistor - 1%")
      (fields
        (field (name "MANUFACTURER PART NUMBER") "R0402_43R_1%_0.0625W_100PPM")
        (field (name "MANUFACTURER") "GENERIC")
        (field (name "AUTHOR") "CERN DEM JLC")
      )
      (libsource (lib "Resistors") (part "Resistor - 1%"))
    )
    (comp (ref "R264")
      (value "43")
      (footprint "RESC1005X40N")
      (description "Resistor - 1%")
      (fields
        (field (name "MANUFACTURER PART NUMBER") "R0402_43R_1%_0.0625W_100PPM")
        (field (name "MANUFACTURER") "GENERIC")
        (field (name "AUTHOR") "CERN DEM JLC")
      )
      (libsource (lib "Resistors") (part "Resistor - 1%"))
    )
    (comp (ref "R265")
      (value "43")
      (footprint "RESC1005X40N")
      (description "Resistor - 1%")
      (fields
        (field (name "MANUFACTURER PART NUMBER") "R0402_43R_1%_0.0625W_100PPM")
        (field (name "MANUFACTURER") "GENERIC")
        (field (name "AUTHOR") "CERN DEM JLC")
      )
      (libsource (lib "Resistors") (part "Resistor - 1%"))
    )
    (comp (ref "R266")
      (value "43")
      (footprint "RESC1005X40N")
      (description "Resistor - 1%")
      (fields
        (field (name "MANUFACTURER PART NUMBER") "R0402_43R_1%_0.0625W_100PPM")
        (field (name "MANUFACTURER") "GENERIC")
        (field (name "AUTHOR") "CERN DEM JLC")
      )
      (libsource (lib "Resistors") (part "Resistor - 1%"))
    )
    (comp (ref "R267")
      (value "43")
      (footprint "RESC1005X40N")
      (description "Resistor - 1%")
      (fields
        (field (name "MANUFACTURER PART NUMBER") "R0402_43R_1%_0.0625W_100PPM")
        (field (name "MANUFACTURER") "GENERIC")
        (field (name "AUTHOR") "CERN DEM JLC")
      )
      (libsource (lib "Resistors") (part "Resistor - 1%"))
    )
    (comp (ref "R268")
      (value "43")
      (footprint "RESC1005X40N")
      (description "Resistor - 1%")
      (fields
        (field (name "MANUFACTURER PART NUMBER") "R0402_43R_1%_0.0625W_100PPM")
        (field (name "MANUFACTURER") "GENERIC")
        (field (name "AUTHOR") "CERN DEM JLC")
      )
      (libsource (lib "Resistors") (part "Resistor - 1%"))
    )
    (comp (ref "R269")
      (value "43")
      (footprint "RESC1005X40N")
      (description "Resistor - 1%")
      (fields
        (field (name "MANUFACTURER PART NUMBER") "R0402_43R_1%_0.0625W_100PPM")
        (field (name "MANUFACTURER") "GENERIC")
        (field (name "AUTHOR") "CERN DEM JLC")
      )
      (libsource (lib "Resistors") (part "Resistor - 1%"))
    )
    (comp (ref "R270")
      (value "43")
      (footprint "RESC1005X40N")
      (description "Resistor - 1%")
      (fields
        (field (name "MANUFACTURER PART NUMBER") "R0402_43R_1%_0.0625W_100PPM")
        (field (name "MANUFACTURER") "GENERIC")
        (field (name "AUTHOR") "CERN DEM JLC")
      )
      (libsource (lib "Resistors") (part "Resistor - 1%"))
    )
    (comp (ref "R271")
      (value "4k7")
      (footprint "RESC1005X40N")
      (description "Resistor - 1%")
      (fields
        (field (name "MANUFACTURER PART NUMBER") "R0402_4K7_1%_0.0625W_100PPM")
        (field (name "MANUFACTURER") "GENERIC")
        (field (name "AUTHOR") "CERN DEM JLC")
      )
      (libsource (lib "Resistors") (part "Resistor - 1%"))
    )
    (comp (ref "R272")
      (value "43")
      (footprint "RESC1005X40N")
      (description "Resistor - 1%")
      (fields
        (field (name "MANUFACTURER PART NUMBER") "R0402_43R_1%_0.0625W_100PPM")
        (field (name "MANUFACTURER") "GENERIC")
        (field (name "AUTHOR") "CERN DEM JLC")
      )
      (libsource (lib "Resistors") (part "Resistor - 1%"))
    )
    (comp (ref "R273")
      (value "43")
      (footprint "RESC1005X40N")
      (description "Resistor - 1%")
      (fields
        (field (name "MANUFACTURER PART NUMBER") "R0402_43R_1%_0.0625W_100PPM")
        (field (name "MANUFACTURER") "GENERIC")
        (field (name "AUTHOR") "CERN DEM JLC")
      )
      (libsource (lib "Resistors") (part "Resistor - 1%"))
    )
    (comp (ref "R274")
      (value "43")
      (footprint "RESC1005X40N")
      (description "Resistor - 1%")
      (fields
        (field (name "MANUFACTURER PART NUMBER") "R0402_43R_1%_0.0625W_100PPM")
        (field (name "MANUFACTURER") "GENERIC")
        (field (name "AUTHOR") "CERN DEM JLC")
      )
      (libsource (lib "Resistors") (part "Resistor - 1%"))
    )
    (comp (ref "R275")
      (value "43")
      (footprint "RESC1005X40N")
      (description "Resistor - 1%")
      (fields
        (field (name "MANUFACTURER PART NUMBER") "R0402_43R_1%_0.0625W_100PPM")
        (field (name "MANUFACTURER") "GENERIC")
        (field (name "AUTHOR") "CERN DEM JLC")
      )
      (libsource (lib "Resistors") (part "Resistor - 1%"))
    )
    (comp (ref "R276")
      (value "240")
      (footprint "RESC1005X40N")
      (description "Resistor - 1%")
      (fields
        (field (name "MANUFACTURER PART NUMBER") "R0402_240R_1%_0.0625W_100PPM")
        (field (name "MANUFACTURER") "GENERIC")
        (field (name "AUTHOR") "CERN DEM JLC")
      )
      (libsource (lib "Resistors") (part "Resistor - 1%"))
    )
    (comp (ref "R277")
      (value "240")
      (footprint "RESC1005X40N")
      (description "Resistor - 1%")
      (fields
        (field (name "MANUFACTURER PART NUMBER") "R0402_240R_1%_0.0625W_100PPM")
        (field (name "MANUFACTURER") "GENERIC")
        (field (name "AUTHOR") "CERN DEM JLC")
      )
      (libsource (lib "Resistors") (part "Resistor - 1%"))
    )
    (comp (ref "R278")
      (value "240")
      (footprint "RESC1005X40N")
      (description "Resistor - 1%")
      (fields
        (field (name "MANUFACTURER PART NUMBER") "R0402_240R_1%_0.0625W_100PPM")
        (field (name "MANUFACTURER") "GENERIC")
        (field (name "AUTHOR") "CERN DEM JLC")
      )
      (libsource (lib "Resistors") (part "Resistor - 1%"))
    )
    (comp (ref "R279")
      (value "240")
      (footprint "RESC1005X40N")
      (description "Resistor - 1%")
      (fields
        (field (name "MANUFACTURER PART NUMBER") "R0402_240R_1%_0.0625W_100PPM")
        (field (name "MANUFACTURER") "GENERIC")
        (field (name "AUTHOR") "CERN DEM JLC")
      )
      (libsource (lib "Resistors") (part "Resistor - 1%"))
    )
    (comp (ref "R280")
      (value "43")
      (footprint "RESC1005X40N")
      (description "Resistor - 1%")
      (fields
        (field (name "MANUFACTURER PART NUMBER") "R0402_43R_1%_0.0625W_100PPM")
        (field (name "MANUFACTURER") "GENERIC")
        (field (name "AUTHOR") "CERN DEM JLC")
      )
      (libsource (lib "Resistors") (part "Resistor - 1%"))
    )
    (comp (ref "R281")
      (value "43")
      (footprint "RESC1005X40N")
      (description "Resistor - 1%")
      (fields
        (field (name "MANUFACTURER PART NUMBER") "R0402_43R_1%_0.0625W_100PPM")
        (field (name "MANUFACTURER") "GENERIC")
        (field (name "AUTHOR") "CERN DEM JLC")
      )
      (libsource (lib "Resistors") (part "Resistor - 1%"))
    )
    (comp (ref "R282")
      (value "43")
      (footprint "RESC1005X40N")
      (description "Resistor - 1%")
      (fields
        (field (name "MANUFACTURER PART NUMBER") "R0402_43R_1%_0.0625W_100PPM")
        (field (name "MANUFACTURER") "GENERIC")
        (field (name "AUTHOR") "CERN DEM JLC")
      )
      (libsource (lib "Resistors") (part "Resistor - 1%"))
    )
    (comp (ref "R283")
      (value "43")
      (footprint "RESC1005X40N")
      (description "Resistor - 1%")
      (fields
        (field (name "MANUFACTURER PART NUMBER") "R0402_43R_1%_0.0625W_100PPM")
        (field (name "MANUFACTURER") "GENERIC")
        (field (name "AUTHOR") "CERN DEM JLC")
      )
      (libsource (lib "Resistors") (part "Resistor - 1%"))
    )
    (comp (ref "R284")
      (value "10k")
      (footprint "RESC1005X40N")
      (description "Resistor - 1%")
      (fields
        (field (name "MANUFACTURER PART NUMBER") "R0402_10K_1%_0.0625W_100PPM")
        (field (name "MANUFACTURER") "GENERIC")
        (field (name "AUTHOR") "CERN DEM JLC")
      )
      (libsource (lib "Resistors") (part "Resistor - 1%"))
    )
    (comp (ref "R285")
      (value "10")
      (footprint "RESC1005X40N")
      (description "Resistor - 1%")
      (fields
        (field (name "MANUFACTURER PART NUMBER") "R0402_10R_1%_0.0625W_200PPM")
        (field (name "MANUFACTURER") "GENERIC")
        (field (name "AUTHOR") "CERN DEM JLC")
      )
      (libsource (lib "Resistors") (part "Resistor - 1%"))
    )
    (comp (ref "R286")
      (value "10k")
      (footprint "RESC1005X40N")
      (description "Resistor - 1%")
      (fields
        (field (name "MANUFACTURER PART NUMBER") "R0402_10K_1%_0.0625W_100PPM")
        (field (name "MANUFACTURER") "GENERIC")
        (field (name "AUTHOR") "CERN DEM JLC")
      )
      (libsource (lib "Resistors") (part "Resistor - 1%"))
    )
  )
  (nets
    (net (code "2") (name "/DDR3_64_A0") (class "Default")
      (node (ref "IC46") (pin "N3") (pinfunction "A0_N3") (pintype "input"))
      (node (ref "IC47") (pin "N3") (pinfunction "A0_N3") (pintype "input"))
      (node (ref "IC48") (pin "N3") (pinfunction "A0_N3") (pintype "input"))
      (node (ref "IC49") (pin "N3") (pinfunction "A0_N3") (pintype "input"))
      (node (ref "R253") (pin "2") (pinfunction "2_2") (pintype "passive"))
    )
    (net (code "3") (name "/DDR3_64_A1") (class "Default")
      (node (ref "IC46") (pin "P7") (pinfunction "A1_P7") (pintype "input"))
      (node (ref "IC47") (pin "P7") (pinfunction "A1_P7") (pintype "input"))
      (node (ref "IC48") (pin "P7") (pinfunction "A1_P7") (pintype "input"))
      (node (ref "IC49") (pin "P7") (pinfunction "A1_P7") (pintype "input"))
      (node (ref "R254") (pin "2") (pinfunction "2_2") (pintype "passive"))
    )
    (net (code "4") (name "/DDR3_64_A2") (class "Default")
      (node (ref "IC46") (pin "P3") (pinfunction "A2_P3") (pintype "input"))
      (node (ref "IC47") (pin "P3") (pinfunction "A2_P3") (pintype "input"))
      (node (ref "IC48") (pin "P3") (pinfunction "A2_P3") (pintype "input"))
      (node (ref "IC49") (pin "P3") (pinfunction "A2_P3") (pintype "input"))
      (node (ref "R255") (pin "2") (pinfunction "2_2") (pintype "passive"))
    )
    (net (code "5") (name "/DDR3_64_A3") (class "Default")
      (node (ref "IC46") (pin "N2") (pinfunction "A3_N2") (pintype "input"))
      (node (ref "IC47") (pin "N2") (pinfunction "A3_N2") (pintype "input"))
      (node (ref "IC48") (pin "N2") (pinfunction "A3_N2") (pintype "input"))
      (node (ref "IC49") (pin "N2") (pinfunction "A3_N2") (pintype "input"))
      (node (ref "R256") (pin "2") (pinfunction "2_2") (pintype "passive"))
    )
    (net (code "6") (name "/DDR3_64_A4") (class "Default")
      (node (ref "IC46") (pin "P8") (pinfunction "A4_P8") (pintype "input"))
      (node (ref "IC47") (pin "P8") (pinfunction "A4_P8") (pintype "input"))
      (node (ref "IC48") (pin "P8") (pinfunction "A4_P8") (pintype "input"))
      (node (ref "IC49") (pin "P8") (pinfunction "A4_P8") (pintype "input"))
      (node (ref "R257") (pin "2") (pinfunction "2_2") (pintype "passive"))
    )
    (net (code "7") (name "/DDR3_64_A5") (class "Default")
      (node (ref "IC46") (pin "P2") (pinfunction "A5_P2") (pintype "input"))
      (node (ref "IC47") (pin "P2") (pinfunction "A5_P2") (pintype "input"))
      (node (ref "IC48") (pin "P2") (pinfunction "A5_P2") (pintype "input"))
      (node (ref "IC49") (pin "P2") (pinfunction "A5_P2") (pintype "input"))
      (node (ref "R258") (pin "2") (pinfunction "2_2") (pintype "passive"))
    )
    (net (code "8") (name "/DDR3_64_A6") (class "Default")
      (node (ref "IC46") (pin "R8") (pinfunction "A6_R8") (pintype "input"))
      (node (ref "IC47") (pin "R8") (pinfunction "A6_R8") (pintype "input"))
      (node (ref "IC48") (pin "R8") (pinfunction "A6_R8") (pintype "input"))
      (node (ref "IC49") (pin "R8") (pinfunction "A6_R8") (pintype "input"))
      (node (ref "R259") (pin "2") (pinfunction "2_2") (pintype "passive"))
    )
    (net (code "9") (name "/DDR3_64_A7") (class "Default")
      (node (ref "IC46") (pin "R2") (pinfunction "A7_R2") (pintype "input"))
      (node (ref "IC47") (pin "R2") (pinfunction "A7_R2") (pintype "input"))
      (node (ref "IC48") (pin "R2") (pinfunction "A7_R2") (pintype "input"))
      (node (ref "IC49") (pin "R2") (pinfunction "A7_R2") (pintype "input"))
      (node (ref "R260") (pin "2") (pinfunction "2_2") (pintype "passive"))
    )
    (net (code "10") (name "/DDR3_64_A8") (class "Default")
      (node (ref "IC46") (pin "T8") (pinfunction "A8_T8") (pintype "input"))
      (node (ref "IC47") (pin "T8") (pinfunction "A8_T8") (pintype "input"))
      (node (ref "IC48") (pin "T8") (pinfunction "A8_T8") (pintype "input"))
      (node (ref "IC49") (pin "T8") (pinfunction "A8_T8") (pintype "input"))
      (node (ref "R261") (pin "2") (pinfunction "2_2") (pintype "passive"))
    )
    (net (code "11") (name "/DDR3_64_A9") (class "Default")
      (node (ref "IC46") (pin "R3") (pinfunction "A9_R3") (pintype "input"))
      (node (ref "IC47") (pin "R3") (pinfunction "A9_R3") (pintype "input"))
      (node (ref "IC48") (pin "R3") (pinfunction "A9_R3") (pintype "input"))
      (node (ref "IC49") (pin "R3") (pinfunction "A9_R3") (pintype "input"))
      (node (ref "R262") (pin "2") (pinfunction "2_2") (pintype "passive"))
    )
    (net (code "12") (name "/DDR3_64_A10") (class "Default")
      (node (ref "IC46") (pin "L7") (pinfunction "A10/AP_L7") (pintype "input"))
      (node (ref "IC47") (pin "L7") (pinfunction "A10/AP_L7") (pintype "input"))
      (node (ref "IC48") (pin "L7") (pinfunction "A10/AP_L7") (pintype "input"))
      (node (ref "IC49") (pin "L7") (pinfunction "A10/AP_L7") (pintype "input"))
      (node (ref "R263") (pin "2") (pinfunction "2_2") (pintype "passive"))
    )
    (net (code "13") (name "/DDR3_64_A11") (class "Default")
      (node (ref "IC46") (pin "R7") (pinfunction "A11_R7") (pintype "input"))
      (node (ref "IC47") (pin "R7") (pinfunction "A11_R7") (pintype "input"))
      (node (ref "IC48") (pin "R7") (pinfunction "A11_R7") (pintype "input"))
      (node (ref "IC49") (pin "R7") (pinfunction "A11_R7") (pintype "input"))
      (node (ref "R264") (pin "2") (pinfunction "2_2") (pintype "passive"))
    )
    (net (code "14") (name "/DDR3_64_A12") (class "Default")
      (node (ref "IC46") (pin "N7") (pinfunction "A12/~{BC}_N7") (pintype "input"))
      (node (ref "IC47") (pin "N7") (pinfunction "A12/~{BC}_N7") (pintype "input"))
      (node (ref "IC48") (pin "N7") (pinfunction "A12/~{BC}_N7") (pintype "input"))
      (node (ref "IC49") (pin "N7") (pinfunction "A12/~{BC}_N7") (pintype "input"))
      (node (ref "R265") (pin "2") (pinfunction "2_2") (pintype "passive"))
    )
    (net (code "15") (name "/DDR3_64_A13") (class "Default")
      (node (ref "IC46") (pin "T3") (pinfunction "A13_T3") (pintype "input"))
      (node (ref "IC47") (pin "T3") (pinfunction "A13_T3") (pintype "input"))
      (node (ref "IC48") (pin "T3") (pinfunction "A13_T3") (pintype "input"))
      (node (ref "IC49") (pin "T3") (pinfunction "A13_T3") (pintype "input"))
      (node (ref "R266") (pin "2") (pinfunction "2_2") (pintype "passive"))
    )
    (net (code "16") (name "/DDR3_64_A14") (class "Default")
      (node (ref "IC46") (pin "T7") (pinfunction "A14_T7") (pintype "passive"))
      (node (ref "IC47") (pin "T7") (pinfunction "A14_T7") (pintype "passive"))
      (node (ref "IC48") (pin "T7") (pinfunction "A14_T7") (pintype "passive"))
      (node (ref "IC49") (pin "T7") (pinfunction "A14_T7") (pintype "passive"))
      (node (ref "R267") (pin "2") (pinfunction "2_2") (pintype "passive"))
    )
    (net (code "18") (name "/DDR3_64_BA0") (class "Default")
      (node (ref "IC46") (pin "M2") (pinfunction "BA0_M2") (pintype "input"))
      (node (ref "IC47") (pin "M2") (pinfunction "BA0_M2") (pintype "input"))
      (node (ref "IC48") (pin "M2") (pinfunction "BA0_M2") (pintype "input"))
      (node (ref "IC49") (pin "M2") (pinfunction "BA0_M2") (pintype "input"))
      (node (ref "R281") (pin "2") (pinfunction "2_2") (pintype "passive"))
    )
    (net (code "19") (name "/DDR3_64_BA1") (class "Default")
      (node (ref "IC46") (pin "N8") (pinfunction "BA1_N8") (pintype "input"))
      (node (ref "IC47") (pin "N8") (pinfunction "BA1_N8") (pintype "input"))
      (node (ref "IC48") (pin "N8") (pinfunction "BA1_N8") (pintype "input"))
      (node (ref "IC49") (pin "N8") (pinfunction "BA1_N8") (pintype "input"))
      (node (ref "R282") (pin "2") (pinfunction "2_2") (pintype "passive"))
    )
    (net (code "20") (name "/DDR3_64_BA2") (class "Default")
      (node (ref "IC46") (pin "M3") (pinfunction "BA2_M3") (pintype "input"))
      (node (ref "IC47") (pin "M3") (pinfunction "BA2_M3") (pintype "input"))
      (node (ref "IC48") (pin "M3") (pinfunction "BA2_M3") (pintype "input"))
      (node (ref "IC49") (pin "M3") (pinfunction "BA2_M3") (pintype "input"))
      (node (ref "R283") (pin "2") (pinfunction "2_2") (pintype "passive"))
    )
    (net (code "21") (name "/DDR3_64_CAS_N") (class "Default")
      (node (ref "IC46") (pin "K3") (pinfunction "~{CAS}_K3") (pintype "input"))
      (node (ref "IC47") (pin "K3") (pinfunction "~{CAS}_K3") (pintype "input"))
      (node (ref "IC48") (pin "K3") (pinfunction "~{CAS}_K3") (pintype "input"))
      (node (ref "IC49") (pin "K3") (pinfunction "~{CAS}_K3") (pintype "input"))
      (node (ref "R273") (pin "2") (pinfunction "2_2") (pintype "passive"))
    )
    (net (code "22") (name "/DDR3_64_CKE") (class "Default")
      (node (ref "IC46") (pin "K9") (pinfunction "CKE_K9") (pintype "input"))
      (node (ref "IC47") (pin "K9") (pinfunction "CKE_K9") (pintype "input"))
      (node (ref "IC48") (pin "K9") (pinfunction "CKE_K9") (pintype "input"))
      (node (ref "IC49") (pin "K9") (pinfunction "CKE_K9") (pintype "input"))
      (node (ref "R270") (pin "2") (pinfunction "2_2") (pintype "passive"))
    )
    (net (code "23") (name "/DDR3_64_CK_N") (class "Default")
      (node (ref "IC46") (pin "K7") (pinfunction "~{CK}_K7") (pintype "input"))
      (node (ref "IC47") (pin "K7") (pinfunction "~{CK}_K7") (pintype "input"))
      (node (ref "IC48") (pin "K7") (pinfunction "~{CK}_K7") (pintype "input"))
      (node (ref "IC49") (pin "K7") (pinfunction "~{CK}_K7") (pintype "input"))
      (node (ref "R269") (pin "2") (pinfunction "2_2") (pintype "passive"))
    )
    (net (code "24") (name "/DDR3_64_CK_P") (class "Default")
      (node (ref "IC46") (pin "J7") (pinfunction "CK_J7") (pintype "input"))
      (node (ref "IC47") (pin "J7") (pinfunction "CK_J7") (pintype "input"))
      (node (ref "IC48") (pin "J7") (pinfunction "CK_J7") (pintype "input"))
      (node (ref "IC49") (pin "J7") (pinfunction "CK_J7") (pintype "input"))
      (node (ref "R268") (pin "2") (pinfunction "2_2") (pintype "passive"))
    )
    (net (code "25") (name "/DDR3_64_CS_N") (class "Default")
      (node (ref "IC46") (pin "L2") (pinfunction "~{CS}_L2") (pintype "input"))
      (node (ref "IC47") (pin "L2") (pinfunction "~{CS}_L2") (pintype "input"))
      (node (ref "IC48") (pin "L2") (pinfunction "~{CS}_L2") (pintype "input"))
      (node (ref "IC49") (pin "L2") (pinfunction "~{CS}_L2") (pintype "input"))
      (node (ref "R274") (pin "2") (pinfunction "2_2") (pintype "passive"))
    )
    (net (code "26") (name "/DDR3_64_DM0") (class "Default")
      (node (ref "IC46") (pin "E7") (pinfunction "LDM_E7") (pintype "input"))
    )
    (net (code "27") (name "/DDR3_64_DM1") (class "Default")
      (node (ref "IC46") (pin "D3") (pinfunction "UDM_D3") (pintype "input"))
    )
    (net (code "28") (name "/DDR3_64_DM2") (class "Default")
      (node (ref "IC47") (pin "E7") (pinfunction "LDM_E7") (pintype "input"))
    )
    (net (code "29") (name "/DDR3_64_DM3") (class "Default")
      (node (ref "IC47") (pin "D3") (pinfunction "UDM_D3") (pintype "input"))
    )
    (net (code "30") (name "/DDR3_64_DM4") (class "Default")
      (node (ref "IC48") (pin "E7") (pinfunction "LDM_E7") (pintype "input"))
    )
    (net (code "31") (name "/DDR3_64_DM5") (class "Default")
      (node (ref "IC48") (pin "D3") (pinfunction "UDM_D3") (pintype "input"))
    )
    (net (code "32") (name "/DDR3_64_DM6") (class "Default")
      (node (ref "IC49") (pin "E7") (pinfunction "LDM_E7") (pintype "input"))
    )
    (net (code "33") (name "/DDR3_64_DM7") (class "Default")
      (node (ref "IC49") (pin "D3") (pinfunction "UDM_D3") (pintype "input"))
    )
    (net (code "35") (name "/DDR3_64_DQ0") (class "Default")
      (node (ref "IC46") (pin "E3") (pinfunction "DQ0_E3") (pintype "bidirectional"))
    )
    (net (code "36") (name "/DDR3_64_DQ1") (class "Default")
      (node (ref "IC46") (pin "F7") (pinfunction "DQ1_F7") (pintype "bidirectional"))
    )
    (net (code "37") (name "/DDR3_64_DQ2") (class "Default")
      (node (ref "IC46") (pin "F2") (pinfunction "DQ2_F2") (pintype "bidirectional"))
    )
    (net (code "38") (name "/DDR3_64_DQ3") (class "Default")
      (node (ref "IC46") (pin "F8") (pinfunction "DQ3_F8") (pintype "bidirectional"))
    )
    (net (code "39") (name "/DDR3_64_DQ4") (class "Default")
      (node (ref "IC46") (pin "H3") (pinfunction "DQ4_H3") (pintype "bidirectional"))
    )
    (net (code "40") (name "/DDR3_64_DQ5") (class "Default")
      (node (ref "IC46") (pin "H8") (pinfunction "DQ5_H8") (pintype "bidirectional"))
    )
    (net (code "41") (name "/DDR3_64_DQ6") (class "Default")
      (node (ref "IC46") (pin "G2") (pinfunction "DQ6_G2") (pintype "bidirectional"))
    )
    (net (code "42") (name "/DDR3_64_DQ7") (class "Default")
      (node (ref "IC46") (pin "H7") (pinfunction "DQ7_H7") (pintype "bidirectional"))
    )
    (net (code "43") (name "/DDR3_64_DQ8") (class "Default")
      (node (ref "IC46") (pin "D7") (pinfunction "DQ8_D7") (pintype "bidirectional"))
    )
    (net (code "44") (name "/DDR3_64_DQ9") (class "Default")
      (node (ref "IC46") (pin "C3") (pinfunction "DQ9_C3") (pintype "bidirectional"))
    )
    (net (code "45") (name "/DDR3_64_DQ10") (class "Default")
      (node (ref "IC46") (pin "C8") (pinfunction "DQ10_C8") (pintype "bidirectional"))
    )
    (net (code "46") (name "/DDR3_64_DQ11") (class "Default")
      (node (ref "IC46") (pin "C2") (pinfunction "DQ11_C2") (pintype "bidirectional"))
    )
    (net (code "47") (name "/DDR3_64_DQ12") (class "Default")
      (node (ref "IC46") (pin "A7") (pinfunction "DQ12_A7") (pintype "bidirectional"))
    )
    (net (code "48") (name "/DDR3_64_DQ13") (class "Default")
      (node (ref "IC46") (pin "A2") (pinfunction "DQ13_A2") (pintype "bidirectional"))
    )
    (net (code "49") (name "/DDR3_64_DQ14") (class "Default")
      (node (ref "IC46") (pin "B8") (pinfunction "DQ14_B8") (pintype "bidirectional"))
    )
    (net (code "50") (name "/DDR3_64_DQ15") (class "Default")
      (node (ref "IC46") (pin "A3") (pinfunction "DQ15_A3") (pintype "bidirectional"))
    )
    (net (code "51") (name "/DDR3_64_DQ16") (class "Default")
      (node (ref "IC47") (pin "E3") (pinfunction "DQ0_E3") (pintype "bidirectional"))
    )
    (net (code "52") (name "/DDR3_64_DQ17") (class "Default")
      (node (ref "IC47") (pin "F7") (pinfunction "DQ1_F7") (pintype "bidirectional"))
    )
    (net (code "53") (name "/DDR3_64_DQ18") (class "Default")
      (node (ref "IC47") (pin "F2") (pinfunction "DQ2_F2") (pintype "bidirectional"))
    )
    (net (code "54") (name "/DDR3_64_DQ19") (class "Default")
      (node (ref "IC47") (pin "F8") (pinfunction "DQ3_F8") (pintype "bidirectional"))
    )
    (net (code "55") (name "/DDR3_64_DQ20") (class "Default")
      (node (ref "IC47") (pin "H3") (pinfunction "DQ4_H3") (pintype "bidirectional"))
    )
    (net (code "56") (name "/DDR3_64_DQ21") (class "Default")
      (node (ref "IC47") (pin "H8") (pinfunction "DQ5_H8") (pintype "bidirectional"))
    )
    (net (code "57") (name "/DDR3_64_DQ22") (class "Default")
      (node (ref "IC47") (pin "G2") (pinfunction "DQ6_G2") (pintype "bidirectional"))
    )
    (net (code "58") (name "/DDR3_64_DQ23") (class "Default")
      (node (ref "IC47") (pin "H7") (pinfunction "DQ7_H7") (pintype "bidirectional"))
    )
    (net (code "59") (name "/DDR3_64_DQ24") (class "Default")
      (node (ref "IC47") (pin "D7") (pinfunction "DQ8_D7") (pintype "bidirectional"))
    )
    (net (code "60") (name "/DDR3_64_DQ25") (class "Default")
      (node (ref "IC47") (pin "C3") (pinfunction "DQ9_C3") (pintype "bidirectional"))
    )
    (net (code "61") (name "/DDR3_64_DQ26") (class "Default")
      (node (ref "IC47") (pin "C8") (pinfunction "DQ10_C8") (pintype "bidirectional"))
    )
    (net (code "62") (name "/DDR3_64_DQ27") (class "Default")
      (node (ref "IC47") (pin "C2") (pinfunction "DQ11_C2") (pintype "bidirectional"))
    )
    (net (code "63") (name "/DDR3_64_DQ28") (class "Default")
      (node (ref "IC47") (pin "A7") (pinfunction "DQ12_A7") (pintype "bidirectional"))
    )
    (net (code "64") (name "/DDR3_64_DQ29") (class "Default")
      (node (ref "IC47") (pin "A2") (pinfunction "DQ13_A2") (pintype "bidirectional"))
    )
    (net (code "65") (name "/DDR3_64_DQ30") (class "Default")
      (node (ref "IC47") (pin "B8") (pinfunction "DQ14_B8") (pintype "bidirectional"))
    )
    (net (code "66") (name "/DDR3_64_DQ31") (class "Default")
      (node (ref "IC47") (pin "A3") (pinfunction "DQ15_A3") (pintype "bidirectional"))
    )
    (net (code "67") (name "/DDR3_64_DQ32") (class "Default")
      (node (ref "IC48") (pin "E3") (pinfunction "DQ0_E3") (pintype "bidirectional"))
    )
    (net (code "68") (name "/DDR3_64_DQ33") (class "Default")
      (node (ref "IC48") (pin "F7") (pinfunction "DQ1_F7") (pintype "bidirectional"))
    )
    (net (code "69") (name "/DDR3_64_DQ34") (class "Default")
      (node (ref "IC48") (pin "F2") (pinfunction "DQ2_F2") (pintype "bidirectional"))
    )
    (net (code "70") (name "/DDR3_64_DQ35") (class "Default")
      (node (ref "IC48") (pin "F8") (pinfunction "DQ3_F8") (pintype "bidirectional"))
    )
    (net (code "71") (name "/DDR3_64_DQ36") (class "Default")
      (node (ref "IC48") (pin "H3") (pinfunction "DQ4_H3") (pintype "bidirectional"))
    )
    (net (code "72") (name "/DDR3_64_DQ37") (class "Default")
      (node (ref "IC48") (pin "H8") (pinfunction "DQ5_H8") (pintype "bidirectional"))
    )
    (net (code "73") (name "/DDR3_64_DQ38") (class "Default")
      (node (ref "IC48") (pin "G2") (pinfunction "DQ6_G2") (pintype "bidirectional"))
    )
    (net (code "74") (name "/DDR3_64_DQ39") (class "Default")
      (node (ref "IC48") (pin "H7") (pinfunction "DQ7_H7") (pintype "bidirectional"))
    )
    (net (code "75") (name "/DDR3_64_DQ40") (class "Default")
      (node (ref "IC48") (pin "D7") (pinfunction "DQ8_D7") (pintype "bidirectional"))
    )
    (net (code "76") (name "/DDR3_64_DQ41") (class "Default")
      (node (ref "IC48") (pin "C3") (pinfunction "DQ9_C3") (pintype "bidirectional"))
    )
    (net (code "77") (name "/DDR3_64_DQ42") (class "Default")
      (node (ref "IC48") (pin "C8") (pinfunction "DQ10_C8") (pintype "bidirectional"))
    )
    (net (code "78") (name "/DDR3_64_DQ43") (class "Default")
      (node (ref "IC48") (pin "C2") (pinfunction "DQ11_C2") (pintype "bidirectional"))
    )
    (net (code "79") (name "/DDR3_64_DQ44") (class "Default")
      (node (ref "IC48") (pin "A7") (pinfunction "DQ12_A7") (pintype "bidirectional"))
    )
    (net (code "80") (name "/DDR3_64_DQ45") (class "Default")
      (node (ref "IC48") (pin "A2") (pinfunction "DQ13_A2") (pintype "bidirectional"))
    )
    (net (code "81") (name "/DDR3_64_DQ46") (class "Default")
      (node (ref "IC48") (pin "B8") (pinfunction "DQ14_B8") (pintype "bidirectional"))
    )
    (net (code "82") (name "/DDR3_64_DQ47") (class "Default")
      (node (ref "IC48") (pin "A3") (pinfunction "DQ15_A3") (pintype "bidirectional"))
    )
    (net (code "83") (name "/DDR3_64_DQ48") (class "Default")
      (node (ref "IC49") (pin "E3") (pinfunction "DQ0_E3") (pintype "bidirectional"))
    )
    (net (code "84") (name "/DDR3_64_DQ49") (class "Default")
      (node (ref "IC49") (pin "F7") (pinfunction "DQ1_F7") (pintype "bidirectional"))
    )
    (net (code "85") (name "/DDR3_64_DQ50") (class "Default")
      (node (ref "IC49") (pin "F2") (pinfunction "DQ2_F2") (pintype "bidirectional"))
    )
    (net (code "86") (name "/DDR3_64_DQ51") (class "Default")
      (node (ref "IC49") (pin "F8") (pinfunction "DQ3_F8") (pintype "bidirectional"))
    )
    (net (code "87") (name "/DDR3_64_DQ52") (class "Default")
      (node (ref "IC49") (pin "H3") (pinfunction "DQ4_H3") (pintype "bidirectional"))
    )
    (net (code "88") (name "/DDR3_64_DQ53") (class "Default")
      (node (ref "IC49") (pin "H8") (pinfunction "DQ5_H8") (pintype "bidirectional"))
    )
    (net (code "89") (name "/DDR3_64_DQ54") (class "Default")
      (node (ref "IC49") (pin "G2") (pinfunction "DQ6_G2") (pintype "bidirectional"))
    )
    (net (code "90") (name "/DDR3_64_DQ55") (class "Default")
      (node (ref "IC49") (pin "H7") (pinfunction "DQ7_H7") (pintype "bidirectional"))
    )
    (net (code "91") (name "/DDR3_64_DQ56") (class "Default")
      (node (ref "IC49") (pin "D7") (pinfunction "DQ8_D7") (pintype "bidirectional"))
    )
    (net (code "92") (name "/DDR3_64_DQ57") (class "Default")
      (node (ref "IC49") (pin "C3") (pinfunction "DQ9_C3") (pintype "bidirectional"))
    )
    (net (code "93") (name "/DDR3_64_DQ58") (class "Default")
      (node (ref "IC49") (pin "C8") (pinfunction "DQ10_C8") (pintype "bidirectional"))
    )
    (net (code "94") (name "/DDR3_64_DQ59") (class "Default")
      (node (ref "IC49") (pin "C2") (pinfunction "DQ11_C2") (pintype "bidirectional"))
    )
    (net (code "95") (name "/DDR3_64_DQ60") (class "Default")
      (node (ref "IC49") (pin "A7") (pinfunction "DQ12_A7") (pintype "bidirectional"))
    )
    (net (code "96") (name "/DDR3_64_DQ61") (class "Default")
      (node (ref "IC49") (pin "A2") (pinfunction "DQ13_A2") (pintype "bidirectional"))
    )
    (net (code "97") (name "/DDR3_64_DQ62") (class "Default")
      (node (ref "IC49") (pin "B8") (pinfunction "DQ14_B8") (pintype "bidirectional"))
    )
    (net (code "98") (name "/DDR3_64_DQ63") (class "Default")
      (node (ref "IC49") (pin "A3") (pinfunction "DQ15_A3") (pintype "bidirectional"))
    )
    (net (code "99") (name "/DDR3_64_DQS0_N") (class "Default")
      (node (ref "IC46") (pin "G3") (pinfunction "~{LDQS}_G3") (pintype "bidirectional"))
    )
    (net (code "100") (name "/DDR3_64_DQS0_P") (class "Default")
      (node (ref "IC46") (pin "F3") (pinfunction "LDQS_F3") (pintype "bidirectional"))
    )
    (net (code "101") (name "/DDR3_64_DQS1_N") (class "Default")
      (node (ref "IC46") (pin "B7") (pinfunction "~{UDQS}_B7") (pintype "bidirectional"))
    )
    (net (code "102") (name "/DDR3_64_DQS1_P") (class "Default")
      (node (ref "IC46") (pin "C7") (pinfunction "UDQS_C7") (pintype "bidirectional"))
    )
    (net (code "103") (name "/DDR3_64_DQS2_N") (class "Default")
      (node (ref "IC47") (pin "G3") (pinfunction "~{LDQS}_G3") (pintype "bidirectional"))
    )
    (net (code "104") (name "/DDR3_64_DQS2_P") (class "Default")
      (node (ref "IC47") (pin "F3") (pinfunction "LDQS_F3") (pintype "bidirectional"))
    )
    (net (code "105") (name "/DDR3_64_DQS3_N") (class "Default")
      (node (ref "IC47") (pin "B7") (pinfunction "~{UDQS}_B7") (pintype "bidirectional"))
    )
    (net (code "106") (name "/DDR3_64_DQS3_P") (class "Default")
      (node (ref "IC47") (pin "C7") (pinfunction "UDQS_C7") (pintype "bidirectional"))
    )
    (net (code "107") (name "/DDR3_64_DQS4_N") (class "Default")
      (node (ref "IC48") (pin "G3") (pinfunction "~{LDQS}_G3") (pintype "bidirectional"))
    )
    (net (code "108") (name "/DDR3_64_DQS4_P") (class "Default")
      (node (ref "IC48") (pin "F3") (pinfunction "LDQS_F3") (pintype "bidirectional"))
    )
    (net (code "109") (name "/DDR3_64_DQS5_N") (class "Default")
      (node (ref "IC48") (pin "B7") (pinfunction "~{UDQS}_B7") (pintype "bidirectional"))
    )
    (net (code "110") (name "/DDR3_64_DQS5_P") (class "Default")
      (node (ref "IC48") (pin "C7") (pinfunction "UDQS_C7") (pintype "bidirectional"))
    )
    (net (code "111") (name "/DDR3_64_DQS6_N") (class "Default")
      (node (ref "IC49") (pin "G3") (pinfunction "~{LDQS}_G3") (pintype "bidirectional"))
    )
    (net (code "112") (name "/DDR3_64_DQS6_P") (class "Default")
      (node (ref "IC49") (pin "F3") (pinfunction "LDQS_F3") (pintype "bidirectional"))
    )
    (net (code "113") (name "/DDR3_64_DQS7_N") (class "Default")
      (node (ref "IC49") (pin "B7") (pinfunction "~{UDQS}_B7") (pintype "bidirectional"))
    )
    (net (code "114") (name "/DDR3_64_DQS7_P") (class "Default")
      (node (ref "IC49") (pin "C7") (pinfunction "UDQS_C7") (pintype "bidirectional"))
    )
    (net (code "116") (name "/DDR3_64_ODT") (class "Default")
      (node (ref "IC46") (pin "K1") (pinfunction "ODT_K1") (pintype "input"))
      (node (ref "IC47") (pin "K1") (pinfunction "ODT_K1") (pintype "input"))
      (node (ref "IC48") (pin "K1") (pinfunction "ODT_K1") (pintype "input"))
      (node (ref "IC49") (pin "K1") (pinfunction "ODT_K1") (pintype "input"))
      (node (ref "R280") (pin "2") (pinfunction "2_2") (pintype "passive"))
    )
    (net (code "117") (name "/DDR3_64_RAS_N") (class "Default")
      (node (ref "IC46") (pin "J3") (pinfunction "~{RAS}_J3") (pintype "input"))
      (node (ref "IC47") (pin "J3") (pinfunction "~{RAS}_J3") (pintype "input"))
      (node (ref "IC48") (pin "J3") (pinfunction "~{RAS}_J3") (pintype "input"))
      (node (ref "IC49") (pin "J3") (pinfunction "~{RAS}_J3") (pintype "input"))
      (node (ref "R272") (pin "2") (pinfunction "2_2") (pintype "passive"))
    )
    (net (code "118") (name "/DDR3_64_RST_N") (class "Default")
      (node (ref "IC46") (pin "T2") (pinfunction "~{RESET}_T2") (pintype "input"))
      (node (ref "IC47") (pin "T2") (pinfunction "~{RESET}_T2") (pintype "input"))
      (node (ref "IC48") (pin "T2") (pinfunction "~{RESET}_T2") (pintype "input"))
      (node (ref "IC49") (pin "T2") (pinfunction "~{RESET}_T2") (pintype "input"))
      (node (ref "R271") (pin "2") (pinfunction "2_2") (pintype "passive"))
    )
    (net (code "119") (name "/DDR3_64_WE_N") (class "Default")
      (node (ref "IC46") (pin "L3") (pinfunction "~{WE}_L3") (pintype "input"))
      (node (ref "IC47") (pin "L3") (pinfunction "~{WE}_L3") (pintype "input"))
      (node (ref "IC48") (pin "L3") (pinfunction "~{WE}_L3") (pintype "input"))
      (node (ref "IC49") (pin "L3") (pinfunction "~{WE}_L3") (pintype "input"))
      (node (ref "R275") (pin "2") (pinfunction "2_2") (pintype "passive"))
    )
    (net (code "120") (name "/PGOOD") (class "Default")
      (node (ref "IC50") (pin "9") (pinfunction "PGOOD_9") (pintype "output"))
    )
    (net (code "122") (name "/SDRAM_REFIN") (class "Default")
      (node (ref "C438") (pin "2") (pinfunction "2_2") (pintype "passive"))
      (node (ref "IC50") (pin "1") (pinfunction "REFIN_1") (pintype "input"))
      (node (ref "R284") (pin "2") (pinfunction "2_2") (pintype "passive"))
      (node (ref "R286") (pin "2") (pinfunction "2_2") (pintype "passive"))
    )
    (net (code "123") (name "/VOSNS") (class "Default")
      (node (ref "C440") (pin "2") (pinfunction "2_2") (pintype "passive"))
      (node (ref "IC50") (pin "5") (pinfunction "VOSNS_5") (pintype "input"))
      (node (ref "R285") (pin "1") (pinfunction "1_1") (pintype "passive"))
    )
    (net (code "124") (name "/ZQ2") (class "Default")
      (node (ref "IC46") (pin "L8") (pinfunction "ZQ_L8") (pintype "input"))
      (node (ref "R279") (pin "2") (pinfunction "2_2") (pintype "passive"))
    )
    (net (code "126") (name "DDR3_64_VREF") (class "Default")
      (node (ref "C398") (pin "1") (pinfunction "1_1") (pintype "passive"))
      (node (ref "C399") (pin "1") (pinfunction "1_1") (pintype "passive"))
      (node (ref "C400") (pin "1") (pinfunction "1_1") (pintype "passive"))
      (node (ref "C401") (pin "1") (pinfunction "1_1") (pintype "passive"))
      (node (ref "C402") (pin "1") (pinfunction "1_1") (pintype "passive"))
      (node (ref "C403") (pin "1") (pinfunction "1_1") (pintype "passive"))
      (node (ref "C404") (pin "1") (pinfunction "1_1") (pintype "passive"))
      (node (ref "C405") (pin "1") (pinfunction "1_1") (pintype "passive"))
      (node (ref "C439") (pin "2") (pinfunction "2_2") (pintype "passive"))
      (node (ref "IC46") (pin "H1") (pinfunction "VREFDQ_H1") (pintype "power_in"))
      (node (ref "IC46") (pin "M8") (pinfunction "VREFCA_M8") (pintype "power_in"))
      (node (ref "IC47") (pin "H1") (pinfunction "VREFDQ_H1") (pintype "power_in"))
      (node (ref "IC47") (pin "M8") (pinfunction "VREFCA_M8") (pintype "power_in"))
      (node (ref "IC48") (pin "H1") (pinfunction "VREFDQ_H1") (pintype "power_in"))
      (node (ref "IC48") (pin "M8") (pinfunction "VREFCA_M8") (pintype "power_in"))
      (node (ref "IC49") (pin "H1") (pinfunction "VREFDQ_H1") (pintype "power_in"))
      (node (ref "IC49") (pin "M8") (pinfunction "VREFCA_M8") (pintype "power_in"))
      (node (ref "IC50") (pin "6") (pinfunction "REFOUT_6") (pintype "output"))
    )
    (net (code "127") (name "GND") (class "Default")
      (node (ref "C398") (pin "2") (pinfunction "2_2") (pintype "passive"))
      (node (ref "C399") (pin "2") (pinfunction "2_2") (pintype "passive"))
      (node (ref "C400") (pin "2") (pinfunction "2_2") (pintype "passive"))
      (node (ref "C401") (pin "2") (pinfunction "2_2") (pintype "passive"))
      (node (ref "C402") (pin "2") (pinfunction "2_2") (pintype "passive"))
      (node (ref "C403") (pin "2") (pinfunction "2_2") (pintype "passive"))
      (node (ref "C404") (pin "2") (pinfunction "2_2") (pintype "passive"))
      (node (ref "C405") (pin "2") (pinfunction "2_2") (pintype "passive"))
      (node (ref "C406") (pin "2") (pinfunction "2_2") (pintype "passive"))
      (node (ref "C407") (pin "2") (pinfunction "2_2") (pintype "passive"))
      (node (ref "C408") (pin "2") (pinfunction "2_2") (pintype "passive"))
      (node (ref "C409") (pin "2") (pinfunction "2_2") (pintype "passive"))
      (node (ref "C410") (pin "2") (pinfunction "2_2") (pintype "passive"))
      (node (ref "C411") (pin "2") (pinfunction "2_2") (pintype "passive"))
      (node (ref "C412") (pin "2") (pinfunction "2_2") (pintype "passive"))
      (node (ref "C413") (pin "2") (pinfunction "2_2") (pintype "passive"))
      (node (ref "C414") (pin "2") (pinfunction "2_2") (pintype "passive"))
      (node (ref "C415") (pin "2") (pinfunction "2_2") (pintype "passive"))
      (node (ref "C416") (pin "2") (pinfunction "2_2") (pintype "passive"))
      (node (ref "C417") (pin "2") (pinfunction "2_2") (pintype "passive"))
      (node (ref "C418") (pin "2") (pinfunction "2_2") (pintype "passive"))
      (node (ref "C419") (pin "2") (pinfunction "2_2") (pintype "passive"))
      (node (ref "C420") (pin "2") (pinfunction "2_2") (pintype "passive"))
      (node (ref "C421") (pin "2") (pinfunction "2_2") (pintype "passive"))
      (node (ref "C422") (pin "2") (pinfunction "2_2") (pintype "passive"))
      (node (ref "C423") (pin "2") (pinfunction "2_2") (pintype "passive"))
      (node (ref "C424") (pin "2") (pinfunction "2_2") (pintype "passive"))
      (node (ref "C425") (pin "2") (pinfunction "2_2") (pintype "passive"))
      (node (ref "C426") (pin "2") (pinfunction "2_2") (pintype "passive"))
      (node (ref "C427") (pin "2") (pinfunction "2_2") (pintype "passive"))
      (node (ref "C428") (pin "2") (pinfunction "2_2") (pintype "passive"))
      (node (ref "C429") (pin "2") (pinfunction "2_2") (pintype "passive"))
      (node (ref "C430") (pin "2") (pinfunction "2_2") (pintype "passive"))
      (node (ref "C431") (pin "1") (pinfunction "1_1") (pintype "passive"))
      (node (ref "C432") (pin "1") (pinfunction "1_1") (pintype "passive"))
      (node (ref "C433") (pin "2") (pinfunction "2_2") (pintype "passive"))
      (node (ref "C434") (pin "2") (pinfunction "2_2") (pintype "passive"))
      (node (ref "C435") (pin "2") (pinfunction "2_2") (pintype "passive"))
      (node (ref "C436") (pin "1") (pinfunction "1_1") (pintype "passive"))
      (node (ref "C437") (pin "2") (pinfunction "2_2") (pintype "passive"))
      (node (ref "C438") (pin "1") (pinfunction "1_1") (pintype "passive"))
      (node (ref "C439") (pin "1") (pinfunction "1_1") (pintype "passive"))
      (node (ref "C440") (pin "1") (pinfunction "1_1") (pintype "passive"))
      (node (ref "C441") (pin "2") (pinfunction "2_2") (pintype "passive"))
      (node (ref "C442") (pin "2") (pinfunction "2_2") (pintype "passive"))
      (node (ref "C443") (pin "2") (pinfunction "2_2") (pintype "passive"))
      (node (ref "C444") (pin "2") (pinfunction "2_2") (pintype "passive"))
      (node (ref "C445") (pin "2") (pinfunction "2_2") (pintype "passive"))
      (node (ref "C446") (pin "2") (pinfunction "2_2") (pintype "passive"))
      (node (ref "C447") (pin "2") (pinfunction "2_2") (pintype "passive"))
      (node (ref "C448") (pin "2") (pinfunction "2_2") (pintype "passive"))
      (node (ref "C449") (pin "2") (pinfunction "2_2") (pintype "passive"))
      (node (ref "C450") (pin "2") (pinfunction "2_2") (pintype "passive"))
      (node (ref "C451") (pin "2") (pinfunction "2_2") (pintype "passive"))
      (node (ref "C452") (pin "2") (pinfunction "2_2") (pintype "passive"))
      (node (ref "C453") (pin "2") (pinfunction "2_2") (pintype "passive"))
      (node (ref "C454") (pin "2") (pinfunction "2_2") (pintype "passive"))
      (node (ref "C455") (pin "2") (pinfunction "2_2") (pintype "passive"))
      (node (ref "C456") (pin "2") (pinfunction "2_2") (pintype "passive"))
      (node (ref "C457") (pin "2") (pinfunction "2_2") (pintype "passive"))
      (node (ref "C458") (pin "2") (pinfunction "2_2") (pintype "passive"))
      (node (ref "C459") (pin "2") (pinfunction "2_2") (pintype "passive"))
      (node (ref "C460") (pin "2") (pinfunction "2_2") (pintype "passive"))
      (node (ref "C461") (pin "2") (pinfunction "2_2") (pintype "passive"))
      (node (ref "C462") (pin "2") (pinfunction "2_2") (pintype "passive"))
      (node (ref "C463") (pin "2") (pinfunction "2_2") (pintype "passive"))
      (node (ref "C464") (pin "2") (pinfunction "2_2") (pintype "passive"))
      (node (ref "C465") (pin "2") (pinfunction "2_2") (pintype "passive"))
      (node (ref "C466") (pin "2") (pinfunction "2_2") (pintype "passive"))
      (node (ref "C467") (pin "2") (pinfunction "2_2") (pintype "passive"))
      (node (ref "C468") (pin "2") (pinfunction "2_2") (pintype "passive"))
      (node (ref "C469") (pin "2") (pinfunction "2_2") (pintype "passive"))
      (node (ref "C470") (pin "2") (pinfunction "2_2") (pintype "passive"))
      (node (ref "C471") (pin "2") (pinfunction "2_2") (pintype "passive"))
      (node (ref "C472") (pin "2") (pinfunction "2_2") (pintype "passive"))
      (node (ref "C473") (pin "2") (pinfunction "2_2") (pintype "passive"))
      (node (ref "C474") (pin "2") (pinfunction "2_2") (pintype "passive"))
      (node (ref "C475") (pin "2") (pinfunction "2_2") (pintype "passive"))
      (node (ref "C476") (pin "2") (pinfunction "2_2") (pintype "passive"))
      (node (ref "C477") (pin "2") (pinfunction "2_2") (pintype "passive"))
      (node (ref "C478") (pin "2") (pinfunction "2_2") (pintype "passive"))
      (node (ref "C479") (pin "2") (pinfunction "2_2") (pintype "passive"))
      (node (ref "C480") (pin "2") (pinfunction "2_2") (pintype "passive"))
      (node (ref "C481") (pin "1") (pinfunction "1_1") (pintype "passive"))
      (node (ref "IC46") (pin "A9") (pinfunction "VSS_A9") (pintype "power_in"))
      (node (ref "IC46") (pin "B1") (pinfunction "VSSQ_B1") (pintype "power_in"))
      (node (ref "IC46") (pin "B3") (pinfunction "VSS_B3") (pintype "power_in"))
      (node (ref "IC46") (pin "B9") (pinfunction "VSSQ_B9") (pintype "power_in"))
      (node (ref "IC46") (pin "D1") (pinfunction "VSSQ_D1") (pintype "power_in"))
      (node (ref "IC46") (pin "D8") (pinfunction "VSSQ_D8") (pintype "power_in"))
      (node (ref "IC46") (pin "E1") (pinfunction "VSS_E1") (pintype "power_in"))
      (node (ref "IC46") (pin "E2") (pinfunction "VSSQ_E2") (pintype "power_in"))
      (node (ref "IC46") (pin "E8") (pinfunction "VSSQ_E8") (pintype "power_in"))
      (node (ref "IC46") (pin "F9") (pinfunction "VSSQ_F9") (pintype "power_in"))
      (node (ref "IC46") (pin "G1") (pinfunction "VSSQ_G1") (pintype "power_in"))
      (node (ref "IC46") (pin "G8") (pinfunction "VSS_G8") (pintype "power_in"))
      (node (ref "IC46") (pin "G9") (pinfunction "VSSQ_G9") (pintype "power_in"))
      (node (ref "IC46") (pin "J2") (pinfunction "VSS_J2") (pintype "power_in"))
      (node (ref "IC46") (pin "J8") (pinfunction "VSS_J8") (pintype "power_in"))
      (node (ref "IC46") (pin "M1") (pinfunction "VSS_M1") (pintype "power_in"))
      (node (ref "IC46") (pin "M9") (pinfunction "VSS_M9") (pintype "power_in"))
      (node (ref "IC46") (pin "P1") (pinfunction "VSS_P1") (pintype "power_in"))
      (node (ref "IC46") (pin "P9") (pinfunction "VSS_P9") (pintype "power_in"))
      (node (ref "IC46") (pin "T1") (pinfunction "VSS_T1") (pintype "power_in"))
      (node (ref "IC46") (pin "T9") (pinfunction "VSS_T9") (pintype "power_in"))
      (node (ref "IC47") (pin "A9") (pinfunction "VSS_A9") (pintype "power_in"))
      (node (ref "IC47") (pin "B1") (pinfunction "VSSQ_B1") (pintype "power_in"))
      (node (ref "IC47") (pin "B3") (pinfunction "VSS_B3") (pintype "power_in"))
      (node (ref "IC47") (pin "B9") (pinfunction "VSSQ_B9") (pintype "power_in"))
      (node (ref "IC47") (pin "D1") (pinfunction "VSSQ_D1") (pintype "power_in"))
      (node (ref "IC47") (pin "D8") (pinfunction "VSSQ_D8") (pintype "power_in"))
      (node (ref "IC47") (pin "E1") (pinfunction "VSS_E1") (pintype "power_in"))
      (node (ref "IC47") (pin "E2") (pinfunction "VSSQ_E2") (pintype "power_in"))
      (node (ref "IC47") (pin "E8") (pinfunction "VSSQ_E8") (pintype "power_in"))
      (node (ref "IC47") (pin "F9") (pinfunction "VSSQ_F9") (pintype "power_in"))
      (node (ref "IC47") (pin "G1") (pinfunction "VSSQ_G1") (pintype "power_in"))
      (node (ref "IC47") (pin "G8") (pinfunction "VSS_G8") (pintype "power_in"))
      (node (ref "IC47") (pin "G9") (pinfunction "VSSQ_G9") (pintype "power_in"))
      (node (ref "IC47") (pin "J2") (pinfunction "VSS_J2") (pintype "power_in"))
      (node (ref "IC47") (pin "J8") (pinfunction "VSS_J8") (pintype "power_in"))
      (node (ref "IC47") (pin "M1") (pinfunction "VSS_M1") (pintype "power_in"))
      (node (ref "IC47") (pin "M9") (pinfunction "VSS_M9") (pintype "power_in"))
      (node (ref "IC47") (pin "P1") (pinfunction "VSS_P1") (pintype "power_in"))
      (node (ref "IC47") (pin "P9") (pinfunction "VSS_P9") (pintype "power_in"))
      (node (ref "IC47") (pin "T1") (pinfunction "VSS_T1") (pintype "power_in"))
      (node (ref "IC47") (pin "T9") (pinfunction "VSS_T9") (pintype "power_in"))
      (node (ref "IC48") (pin "A9") (pinfunction "VSS_A9") (pintype "power_in"))
      (node (ref "IC48") (pin "B1") (pinfunction "VSSQ_B1") (pintype "power_in"))
      (node (ref "IC48") (pin "B3") (pinfunction "VSS_B3") (pintype "power_in"))
      (node (ref "IC48") (pin "B9") (pinfunction "VSSQ_B9") (pintype "power_in"))
      (node (ref "IC48") (pin "D1") (pinfunction "VSSQ_D1") (pintype "power_in"))
      (node (ref "IC48") (pin "D8") (pinfunction "VSSQ_D8") (pintype "power_in"))
      (node (ref "IC48") (pin "E1") (pinfunction "VSS_E1") (pintype "power_in"))
      (node (ref "IC48") (pin "E2") (pinfunction "VSSQ_E2") (pintype "power_in"))
      (node (ref "IC48") (pin "E8") (pinfunction "VSSQ_E8") (pintype "power_in"))
      (node (ref "IC48") (pin "F9") (pinfunction "VSSQ_F9") (pintype "power_in"))
      (node (ref "IC48") (pin "G1") (pinfunction "VSSQ_G1") (pintype "power_in"))
      (node (ref "IC48") (pin "G8") (pinfunction "VSS_G8") (pintype "power_in"))
      (node (ref "IC48") (pin "G9") (pinfunction "VSSQ_G9") (pintype "power_in"))
      (node (ref "IC48") (pin "J2") (pinfunction "VSS_J2") (pintype "power_in"))
      (node (ref "IC48") (pin "J8") (pinfunction "VSS_J8") (pintype "power_in"))
      (node (ref "IC48") (pin "M1") (pinfunction "VSS_M1") (pintype "power_in"))
      (node (ref "IC48") (pin "M9") (pinfunction "VSS_M9") (pintype "power_in"))
      (node (ref "IC48") (pin "P1") (pinfunction "VSS_P1") (pintype "power_in"))
      (node (ref "IC48") (pin "P9") (pinfunction "VSS_P9") (pintype "power_in"))
      (node (ref "IC48") (pin "T1") (pinfunction "VSS_T1") (pintype "power_in"))
      (node (ref "IC48") (pin "T9") (pinfunction "VSS_T9") (pintype "power_in"))
      (node (ref "IC49") (pin "A9") (pinfunction "VSS_A9") (pintype "power_in"))
      (node (ref "IC49") (pin "B1") (pinfunction "VSSQ_B1") (pintype "power_in"))
      (node (ref "IC49") (pin "B3") (pinfunction "VSS_B3") (pintype "power_in"))
      (node (ref "IC49") (pin "B9") (pinfunction "VSSQ_B9") (pintype "power_in"))
      (node (ref "IC49") (pin "D1") (pinfunction "VSSQ_D1") (pintype "power_in"))
      (node (ref "IC49") (pin "D8") (pinfunction "VSSQ_D8") (pintype "power_in"))
      (node (ref "IC49") (pin "E1") (pinfunction "VSS_E1") (pintype "power_in"))
      (node (ref "IC49") (pin "E2") (pinfunction "VSSQ_E2") (pintype "power_in"))
      (node (ref "IC49") (pin "E8") (pinfunction "VSSQ_E8") (pintype "power_in"))
      (node (ref "IC49") (pin "F9") (pinfunction "VSSQ_F9") (pintype "power_in"))
      (node (ref "IC49") (pin "G1") (pinfunction "VSSQ_G1") (pintype "power_in"))
      (node (ref "IC49") (pin "G8") (pinfunction "VSS_G8") (pintype "power_in"))
      (node (ref "IC49") (pin "G9") (pinfunction "VSSQ_G9") (pintype "power_in"))
      (node (ref "IC49") (pin "J2") (pinfunction "VSS_J2") (pintype "power_in"))
      (node (ref "IC49") (pin "J8") (pinfunction "VSS_J8") (pintype "power_in"))
      (node (ref "IC49") (pin "M1") (pinfunction "VSS_M1") (pintype "power_in"))
      (node (ref "IC49") (pin "M9") (pinfunction "VSS_M9") (pintype "power_in"))
      (node (ref "IC49") (pin "P1") (pinfunction "VSS_P1") (pintype "power_in"))
      (node (ref "IC49") (pin "P9") (pinfunction "VSS_P9") (pintype "power_in"))
      (node (ref "IC49") (pin "T1") (pinfunction "VSS_T1") (pintype "power_in"))
      (node (ref "IC49") (pin "T9") (pinfunction "VSS_T9") (pintype "power_in"))
      (node (ref "IC50") (pin "11") (pinfunction "EP_11") (pintype "power_in"))
      (node (ref "IC50") (pin "4") (pinfunction "PGND_4") (pintype "power_in"))
      (node (ref "IC50") (pin "8") (pinfunction "GND_8") (pintype "power_in"))
      (node (ref "R271") (pin "1") (pinfunction "1_1") (pintype "passive"))
      (node (ref "R276") (pin "1") (pinfunction "1_1") (pintype "passive"))
      (node (ref "R277") (pin "1") (pinfunction "1_1") (pintype "passive"))
      (node (ref "R278") (pin "1") (pinfunction "1_1") (pintype "passive"))
      (node (ref "R279") (pin "1") (pinfunction "1_1") (pintype "passive"))
      (node (ref "R286") (pin "1") (pinfunction "1_1") (pintype "passive"))
    )
    (net (code "128") (name "Net-(IC47-ZQ)") (class "Default")
      (node (ref "IC47") (pin "L8") (pinfunction "ZQ_L8") (pintype "input"))
      (node (ref "R276") (pin "2") (pinfunction "2_2") (pintype "passive"))
    )
    (net (code "129") (name "Net-(IC48-ZQ)") (class "Default")
      (node (ref "IC48") (pin "L8") (pinfunction "ZQ_L8") (pintype "input"))
      (node (ref "R277") (pin "2") (pinfunction "2_2") (pintype "passive"))
    )
    (net (code "130") (name "Net-(IC49-ZQ)") (class "Default")
      (node (ref "IC49") (pin "L8") (pinfunction "ZQ_L8") (pintype "input"))
      (node (ref "R278") (pin "2") (pinfunction "2_2") (pintype "passive"))
    )
    (net (code "131") (name "P1V5") (class "Default")
      (node (ref "C406") (pin "1") (pinfunction "1_1") (pintype "passive"))
      (node (ref "C407") (pin "1") (pinfunction "1_1") (pintype "passive"))
      (node (ref "C408") (pin "1") (pinfunction "1_1") (pintype "passive"))
      (node (ref "C409") (pin "1") (pinfunction "1_1") (pintype "passive"))
      (node (ref "C410") (pin "1") (pinfunction "1_1") (pintype "passive"))
      (node (ref "C411") (pin "1") (pinfunction "1_1") (pintype "passive"))
      (node (ref "C412") (pin "1") (pinfunction "1_1") (pintype "passive"))
      (node (ref "C413") (pin "1") (pinfunction "1_1") (pintype "passive"))
      (node (ref "C414") (pin "1") (pinfunction "1_1") (pintype "passive"))
      (node (ref "C415") (pin "1") (pinfunction "1_1") (pintype "passive"))
      (node (ref "C417") (pin "1") (pinfunction "1_1") (pintype "passive"))
      (node (ref "C418") (pin "1") (pinfunction "1_1") (pintype "passive"))
      (node (ref "C419") (pin "1") (pinfunction "1_1") (pintype "passive"))
      (node (ref "C420") (pin "1") (pinfunction "1_1") (pintype "passive"))
      (node (ref "C421") (pin "1") (pinfunction "1_1") (pintype "passive"))
      (node (ref "C422") (pin "1") (pinfunction "1_1") (pintype "passive"))
      (node (ref "C423") (pin "1") (pinfunction "1_1") (pintype "passive"))
      (node (ref "C424") (pin "1") (pinfunction "1_1") (pintype "passive"))
      (node (ref "C425") (pin "1") (pinfunction "1_1") (pintype "passive"))
      (node (ref "C426") (pin "1") (pinfunction "1_1") (pintype "passive"))
      (node (ref "C427") (pin "1") (pinfunction "1_1") (pintype "passive"))
      (node (ref "C428") (pin "1") (pinfunction "1_1") (pintype "passive"))
      (node (ref "C429") (pin "1") (pinfunction "1_1") (pintype "passive"))
      (node (ref "C430") (pin "1") (pinfunction "1_1") (pintype "passive"))
      (node (ref "C433") (pin "1") (pinfunction "1_1") (pintype "passive"))
      (node (ref "C434") (pin "1") (pinfunction "1_1") (pintype "passive"))
      (node (ref "C435") (pin "1") (pinfunction "1_1") (pintype "passive"))
      (node (ref "C436") (pin "2") (pinfunction "2_2") (pintype "passive"))
      (node (ref "C437") (pin "1") (pinfunction "1_1") (pintype "passive"))
      (node (ref "C441") (pin "1") (pinfunction "1_1") (pintype "passive"))
      (node (ref "C442") (pin "1") (pinfunction "1_1") (pintype "passive"))
      (node (ref "C443") (pin "1") (pinfunction "1_1") (pintype "passive"))
      (node (ref "C444") (pin "1") (pinfunction "1_1") (pintype "passive"))
      (node (ref "C445") (pin "1") (pinfunction "1_1") (pintype "passive"))
      (node (ref "C450") (pin "1") (pinfunction "1_1") (pintype "passive"))
      (node (ref "C451") (pin "1") (pinfunction "1_1") (pintype "passive"))
      (node (ref "C452") (pin "1") (pinfunction "1_1") (pintype "passive"))
      (node (ref "C453") (pin "1") (pinfunction "1_1") (pintype "passive"))
      (node (ref "C454") (pin "1") (pinfunction "1_1") (pintype "passive"))
      (node (ref "C456") (pin "1") (pinfunction "1_1") (pintype "passive"))
      (node (ref "C457") (pin "1") (pinfunction "1_1") (pintype "passive"))
      (node (ref "C458") (pin "1") (pinfunction "1_1") (pintype "passive"))
      (node (ref "C459") (pin "1") (pinfunction "1_1") (pintype "passive"))
      (node (ref "C460") (pin "1") (pinfunction "1_1") (pintype "passive"))
      (node (ref "C465") (pin "1") (pinfunction "1_1") (pintype "passive"))
      (node (ref "C466") (pin "1") (pinfunction "1_1") (pintype "passive"))
      (node (ref "C467") (pin "1") (pinfunction "1_1") (pintype "passive"))
      (node (ref "C468") (pin "1") (pinfunction "1_1") (pintype "passive"))
      (node (ref "C469") (pin "1") (pinfunction "1_1") (pintype "passive"))
      (node (ref "C474") (pin "1") (pinfunction "1_1") (pintype "passive"))
      (node (ref "C475") (pin "1") (pinfunction "1_1") (pintype "passive"))
      (node (ref "C476") (pin "1") (pinfunction "1_1") (pintype "passive"))
      (node (ref "C477") (pin "1") (pinfunction "1_1") (pintype "passive"))
      (node (ref "C478") (pin "1") (pinfunction "1_1") (pintype "passive"))
      (node (ref "C479") (pin "1") (pinfunction "1_1") (pintype "passive"))
      (node (ref "C480") (pin "1") (pinfunction "1_1") (pintype "passive"))
      (node (ref "C481") (pin "2") (pinfunction "2_2") (pintype "passive"))
      (node (ref "IC46") (pin "A1") (pinfunction "VDDQ_A1") (pintype "power_in"))
      (node (ref "IC46") (pin "A8") (pinfunction "VDDQ_A8") (pintype "power_in"))
      (node (ref "IC46") (pin "B2") (pinfunction "VDD_B2") (pintype "power_in"))
      (node (ref "IC46") (pin "C1") (pinfunction "VDDQ_C1") (pintype "power_in"))
      (node (ref "IC46") (pin "C9") (pinfunction "VDDQ_C9") (pintype "power_in"))
      (node (ref "IC46") (pin "D2") (pinfunction "VDDQ_D2") (pintype "power_in"))
      (node (ref "IC46") (pin "D9") (pinfunction "VDD_D9") (pintype "power_in"))
      (node (ref "IC46") (pin "E9") (pinfunction "VDDQ_E9") (pintype "power_in"))
      (node (ref "IC46") (pin "F1") (pinfunction "VDDQ_F1") (pintype "power_in"))
      (node (ref "IC46") (pin "G7") (pinfunction "VDD_G7") (pintype "power_in"))
      (node (ref "IC46") (pin "H2") (pinfunction "VDDQ_H2") (pintype "power_in"))
      (node (ref "IC46") (pin "H9") (pinfunction "VDDQ_H9") (pintype "power_in"))
      (node (ref "IC46") (pin "K2") (pinfunction "VDD_K2") (pintype "power_in"))
      (node (ref "IC46") (pin "K8") (pinfunction "VDD_K8") (pintype "power_in"))
      (node (ref "IC46") (pin "N1") (pinfunction "VDD_N1") (pintype "power_in"))
      (node (ref "IC46") (pin "N9") (pinfunction "VDD_N9") (pintype "power_in"))
      (node (ref "IC46") (pin "R1") (pinfunction "VDD_R1") (pintype "power_in"))
      (node (ref "IC46") (pin "R9") (pinfunction "VDD_R9") (pintype "power_in"))
      (node (ref "IC47") (pin "A1") (pinfunction "VDDQ_A1") (pintype "power_in"))
      (node (ref "IC47") (pin "A8") (pinfunction "VDDQ_A8") (pintype "power_in"))
      (node (ref "IC47") (pin "B2") (pinfunction "VDD_B2") (pintype "power_in"))
      (node (ref "IC47") (pin "C1") (pinfunction "VDDQ_C1") (pintype "power_in"))
      (node (ref "IC47") (pin "C9") (pinfunction "VDDQ_C9") (pintype "power_in"))
      (node (ref "IC47") (pin "D2") (pinfunction "VDDQ_D2") (pintype "power_in"))
      (node (ref "IC47") (pin "D9") (pinfunction "VDD_D9") (pintype "power_in"))
      (node (ref "IC47") (pin "E9") (pinfunction "VDDQ_E9") (pintype "power_in"))
      (node (ref "IC47") (pin "F1") (pinfunction "VDDQ_F1") (pintype "power_in"))
      (node (ref "IC47") (pin "G7") (pinfunction "VDD_G7") (pintype "power_in"))
      (node (ref "IC47") (pin "H2") (pinfunction "VDDQ_H2") (pintype "power_in"))
      (node (ref "IC47") (pin "H9") (pinfunction "VDDQ_H9") (pintype "power_in"))
      (node (ref "IC47") (pin "K2") (pinfunction "VDD_K2") (pintype "power_in"))
      (node (ref "IC47") (pin "K8") (pinfunction "VDD_K8") (pintype "power_in"))
      (node (ref "IC47") (pin "N1") (pinfunction "VDD_N1") (pintype "power_in"))
      (node (ref "IC47") (pin "N9") (pinfunction "VDD_N9") (pintype "power_in"))
      (node (ref "IC47") (pin "R1") (pinfunction "VDD_R1") (pintype "power_in"))
      (node (ref "IC47") (pin "R9") (pinfunction "VDD_R9") (pintype "power_in"))
      (node (ref "IC48") (pin "A1") (pinfunction "VDDQ_A1") (pintype "power_in"))
      (node (ref "IC48") (pin "A8") (pinfunction "VDDQ_A8") (pintype "power_in"))
      (node (ref "IC48") (pin "B2") (pinfunction "VDD_B2") (pintype "power_in"))
      (node (ref "IC48") (pin "C1") (pinfunction "VDDQ_C1") (pintype "power_in"))
      (node (ref "IC48") (pin "C9") (pinfunction "VDDQ_C9") (pintype "power_in"))
      (node (ref "IC48") (pin "D2") (pinfunction "VDDQ_D2") (pintype "power_in"))
      (node (ref "IC48") (pin "D9") (pinfunction "VDD_D9") (pintype "power_in"))
      (node (ref "IC48") (pin "E9") (pinfunction "VDDQ_E9") (pintype "power_in"))
      (node (ref "IC48") (pin "F1") (pinfunction "VDDQ_F1") (pintype "power_in"))
      (node (ref "IC48") (pin "G7") (pinfunction "VDD_G7") (pintype "power_in"))
      (node (ref "IC48") (pin "H2") (pinfunction "VDDQ_H2") (pintype "power_in"))
      (node (ref "IC48") (pin "H9") (pinfunction "VDDQ_H9") (pintype "power_in"))
      (node (ref "IC48") (pin "K2") (pinfunction "VDD_K2") (pintype "power_in"))
      (node (ref "IC48") (pin "K8") (pinfunction "VDD_K8") (pintype "power_in"))
      (node (ref "IC48") (pin "N1") (pinfunction "VDD_N1") (pintype "power_in"))
      (node (ref "IC48") (pin "N9") (pinfunction "VDD_N9") (pintype "power_in"))
      (node (ref "IC48") (pin "R1") (pinfunction "VDD_R1") (pintype "power_in"))
      (node (ref "IC48") (pin "R9") (pinfunction "VDD_R9") (pintype "power_in"))
      (node (ref "IC49") (pin "A1") (pinfunction "VDDQ_A1") (pintype "power_in"))
      (node (ref "IC49") (pin "A8") (pinfunction "VDDQ_A8") (pintype "power_in"))
      (node (ref "IC49") (pin "B2") (pinfunction "VDD_B2") (pintype "power_in"))
      (node (ref "IC49") (pin "C1") (pinfunction "VDDQ_C1") (pintype "power_in"))
      (node (ref "IC49") (pin "C9") (pinfunction "VDDQ_C9") (pintype "power_in"))
      (node (ref "IC49") (pin "D2") (pinfunction "VDDQ_D2") (pintype "power_in"))
      (node (ref "IC49") (pin "D9") (pinfunction "VDD_D9") (pintype "power_in"))
      (node (ref "IC49") (pin "E9") (pinfunction "VDDQ_E9") (pintype "power_in"))
      (node (ref "IC49") (pin "F1") (pinfunction "VDDQ_F1") (pintype "power_in"))
      (node (ref "IC49") (pin "G7") (pinfunction "VDD_G7") (pintype "power_in"))
      (node (ref "IC49") (pin "H2") (pinfunction "VDDQ_H2") (pintype "power_in"))
      (node (ref "IC49") (pin "H9") (pinfunction "VDDQ_H9") (pintype "power_in"))
      (node (ref "IC49") (pin "K2") (pinfunction "VDD_K2") (pintype "power_in"))
      (node (ref "IC49") (pin "K8") (pinfunction "VDD_K8") (pintype "power_in"))
      (node (ref "IC49") (pin "N1") (pinfunction "VDD_N1") (pintype "power_in"))
      (node (ref "IC49") (pin "N9") (pinfunction "VDD_N9") (pintype "power_in"))
      (node (ref "IC49") (pin "R1") (pinfunction "VDD_R1") (pintype "power_in"))
      (node (ref "IC49") (pin "R9") (pinfunction "VDD_R9") (pintype "power_in"))
      (node (ref "IC50") (pin "2") (pinfunction "VLDOIN_2") (pintype "input"))
      (node (ref "R284") (pin "1") (pinfunction "1_1") (pintype "passive"))
    )
    (net (code "132") (name "P3V3") (class "Default")
      (node (ref "C416") (pin "1") (pinfunction "1_1") (pintype "passive"))
      (node (ref "IC50") (pin "10") (pinfunction "VIN_10") (pintype "input"))
      (node (ref "IC50") (pin "7") (pinfunction "EN_7") (pintype "input"))
    )
    (net (code "133") (name "VTT64") (class "Default")
      (node (ref "C431") (pin "2") (pinfunction "2_2") (pintype "passive"))
      (node (ref "C432") (pin "2") (pinfunction "2_2") (pintype "passive"))
      (node (ref "C446") (pin "1") (pinfunction "1_1") (pintype "passive"))
      (node (ref "C447") (pin "1") (pinfunction "1_1") (pintype "passive"))
      (node (ref "C448") (pin "1") (pinfunction "1_1") (pintype "passive"))
      (node (ref "C449") (pin "1") (pinfunction "1_1") (pintype "passive"))
      (node (ref "C455") (pin "1") (pinfunction "1_1") (pintype "passive"))
      (node (ref "C461") (pin "1") (pinfunction "1_1") (pintype "passive"))
      (node (ref "C462") (pin "1") (pinfunction "1_1") (pintype "passive"))
      (node (ref "C463") (pin "1") (pinfunction "1_1") (pintype "passive"))
      (node (ref "C464") (pin "1") (pinfunction "1_1") (pintype "passive"))
      (node (ref "C470") (pin "1") (pinfunction "1_1") (pintype "passive"))
      (node (ref "C471") (pin "1") (pinfunction "1_1") (pintype "passive"))
      (node (ref "C472") (pin "1") (pinfunction "1_1") (pintype "passive"))
      (node (ref "C473") (pin "1") (pinfunction "1_1") (pintype "passive"))
      (node (ref "IC50") (pin "3") (pinfunction "VO_3") (pintype "power_in"))
      (node (ref "R253") (pin "1") (pinfunction "1_1") (pintype "passive"))
      (node (ref "R254") (pin "1") (pinfunction "1_1") (pintype "passive"))
      (node (ref "R255") (pin "1") (pinfunction "1_1") (pintype "passive"))
      (node (ref "R256") (pin "1") (pinfunction "1_1") (pintype "passive"))
      (node (ref "R257") (pin "1") (pinfunction "1_1") (pintype "passive"))
      (node (ref "R258") (pin "1") (pinfunction "1_1") (pintype "passive"))
      (node (ref "R259") (pin "1") (pinfunction "1_1") (pintype "passive"))
      (node (ref "R260") (pin "1") (pinfunction "1_1") (pintype "passive"))
      (node (ref "R261") (pin "1") (pinfunction "1_1") (pintype "passive"))
      (node (ref "R262") (pin "1") (pinfunction "1_1") (pintype "passive"))
      (node (ref "R263") (pin "1") (pinfunction "1_1") (pintype "passive"))
      (node (ref "R264") (pin "1") (pinfunction "1_1") (pintype "passive"))
      (node (ref "R265") (pin "1") (pinfunction "1_1") (pintype "passive"))
      (node (ref "R266") (pin "1") (pinfunction "1_1") (pintype "passive"))
      (node (ref "R267") (pin "1") (pinfunction "1_1") (pintype "passive"))
      (node (ref "R268") (pin "1") (pinfunction "1_1") (pintype "passive"))
      (node (ref "R269") (pin "1") (pinfunction "1_1") (pintype "passive"))
      (node (ref "R270") (pin "1") (pinfunction "1_1") (pintype "passive"))
      (node (ref "R272") (pin "1") (pinfunction "1_1") (pintype "passive"))
      (node (ref "R273") (pin "1") (pinfunction "1_1") (pintype "passive"))
      (node (ref "R274") (pin "1") (pinfunction "1_1") (pintype "passive"))
      (node (ref "R275") (pin "1") (pinfunction "1_1") (pintype "passive"))
      (node (ref "R280") (pin "1") (pinfunction "1_1") (pintype "passive"))
      (node (ref "R281") (pin "1") (pinfunction "1_1") (pintype "passive"))
      (node (ref "R282") (pin "1") (pinfunction "1_1") (pintype "passive"))
      (node (ref "R283") (pin "1") (pinfunction "1_1") (pintype "passive"))
      (node (ref "R285") (pin "2") (pinfunction "2_2") (pintype "passive"))
    )
    (net (code "134") (name "unconnected-(IC46-NC-PadJ1)") (class "Default")
      (node (ref "IC46") (pin "J1") (pinfunction "NC_J1") (pintype "passive+no_connect"))
    )
    (net (code "135") (name "unconnected-(IC46-NC-PadJ9)") (class "Default")
      (node (ref "IC46") (pin "J9") (pinfunction "NC_J9") (pintype "passive+no_connect"))
    )
    (net (code "136") (name "unconnected-(IC46-NC-PadL1)") (class "Default")
      (node (ref "IC46") (pin "L1") (pinfunction "NC_L1") (pintype "passive+no_connect"))
    )
    (net (code "137") (name "unconnected-(IC46-NC-PadL9)") (class "Default")
      (node (ref "IC46") (pin "L9") (pinfunction "NC_L9") (pintype "passive+no_connect"))
    )
    (net (code "138") (name "unconnected-(IC46-NC-PadM7)") (class "Default")
      (node (ref "IC46") (pin "M7") (pinfunction "NC_M7") (pintype "passive+no_connect"))
    )
    (net (code "139") (name "unconnected-(IC47-NC-PadJ1)") (class "Default")
      (node (ref "IC47") (pin "J1") (pinfunction "NC_J1") (pintype "passive+no_connect"))
    )
    (net (code "140") (name "unconnected-(IC47-NC-PadJ9)") (class "Default")
      (node (ref "IC47") (pin "J9") (pinfunction "NC_J9") (pintype "passive+no_connect"))
    )
    (net (code "141") (name "unconnected-(IC47-NC-PadL1)") (class "Default")
      (node (ref "IC47") (pin "L1") (pinfunction "NC_L1") (pintype "passive+no_connect"))
    )
    (net (code "142") (name "unconnected-(IC47-NC-PadL9)") (class "Default")
      (node (ref "IC47") (pin "L9") (pinfunction "NC_L9") (pintype "passive+no_connect"))
    )
    (net (code "143") (name "unconnected-(IC47-NC-PadM7)") (class "Default")
      (node (ref "IC47") (pin "M7") (pinfunction "NC_M7") (pintype "passive+no_connect"))
    )
    (net (code "144") (name "unconnected-(IC48-NC-PadJ1)") (class "Default")
      (node (ref "IC48") (pin "J1") (pinfunction "NC_J1") (pintype "passive+no_connect"))
    )
    (net (code "145") (name "unconnected-(IC48-NC-PadJ9)") (class "Default")
      (node (ref "IC48") (pin "J9") (pinfunction "NC_J9") (pintype "passive+no_connect"))
    )
    (net (code "146") (name "unconnected-(IC48-NC-PadL1)") (class "Default")
      (node (ref "IC48") (pin "L1") (pinfunction "NC_L1") (pintype "passive+no_connect"))
    )
    (net (code "147") (name "unconnected-(IC48-NC-PadL9)") (class "Default")
      (node (ref "IC48") (pin "L9") (pinfunction "NC_L9") (pintype "passive+no_connect"))
    )
    (net (code "148") (name "unconnected-(IC48-NC-PadM7)") (class "Default")
      (node (ref "IC48") (pin "M7") (pinfunction "NC_M7") (pintype "passive+no_connect"))
    )
    (net (code "149") (name "unconnected-(IC49-NC-PadJ1)") (class "Default")
      (node (ref "IC49") (pin "J1") (pinfunction "NC_J1") (pintype "passive+no_connect"))
    )
    (net (code "150") (name "unconnected-(IC49-NC-PadJ9)") (class "Default")
      (node (ref "IC49") (pin "J9") (pinfunction "NC_J9") (pintype "passive+no_connect"))
    )
    (net (code "151") (name "unconnected-(IC49-NC-PadL1)") (class "Default")
      (node (ref "IC49") (pin "L1") (pinfunction "NC_L1") (pintype "passive+no_connect"))
    )
    (net (code "152") (name "unconnected-(IC49-NC-PadL9)") (class "Default")
      (node (ref "IC49") (pin "L9") (pinfunction "NC_L9") (pintype "passive+no_connect"))
    )
    (net (code "153") (name "unconnected-(IC49-NC-PadM7)") (class "Default")
      (node (ref "IC49") (pin "M7") (pinfunction "NC_M7") (pintype "passive+no_connect"))
    )
  )
)
